# csa_ultrabus_v2.net
KiCad netlist of a schematic drawn in EAGLE
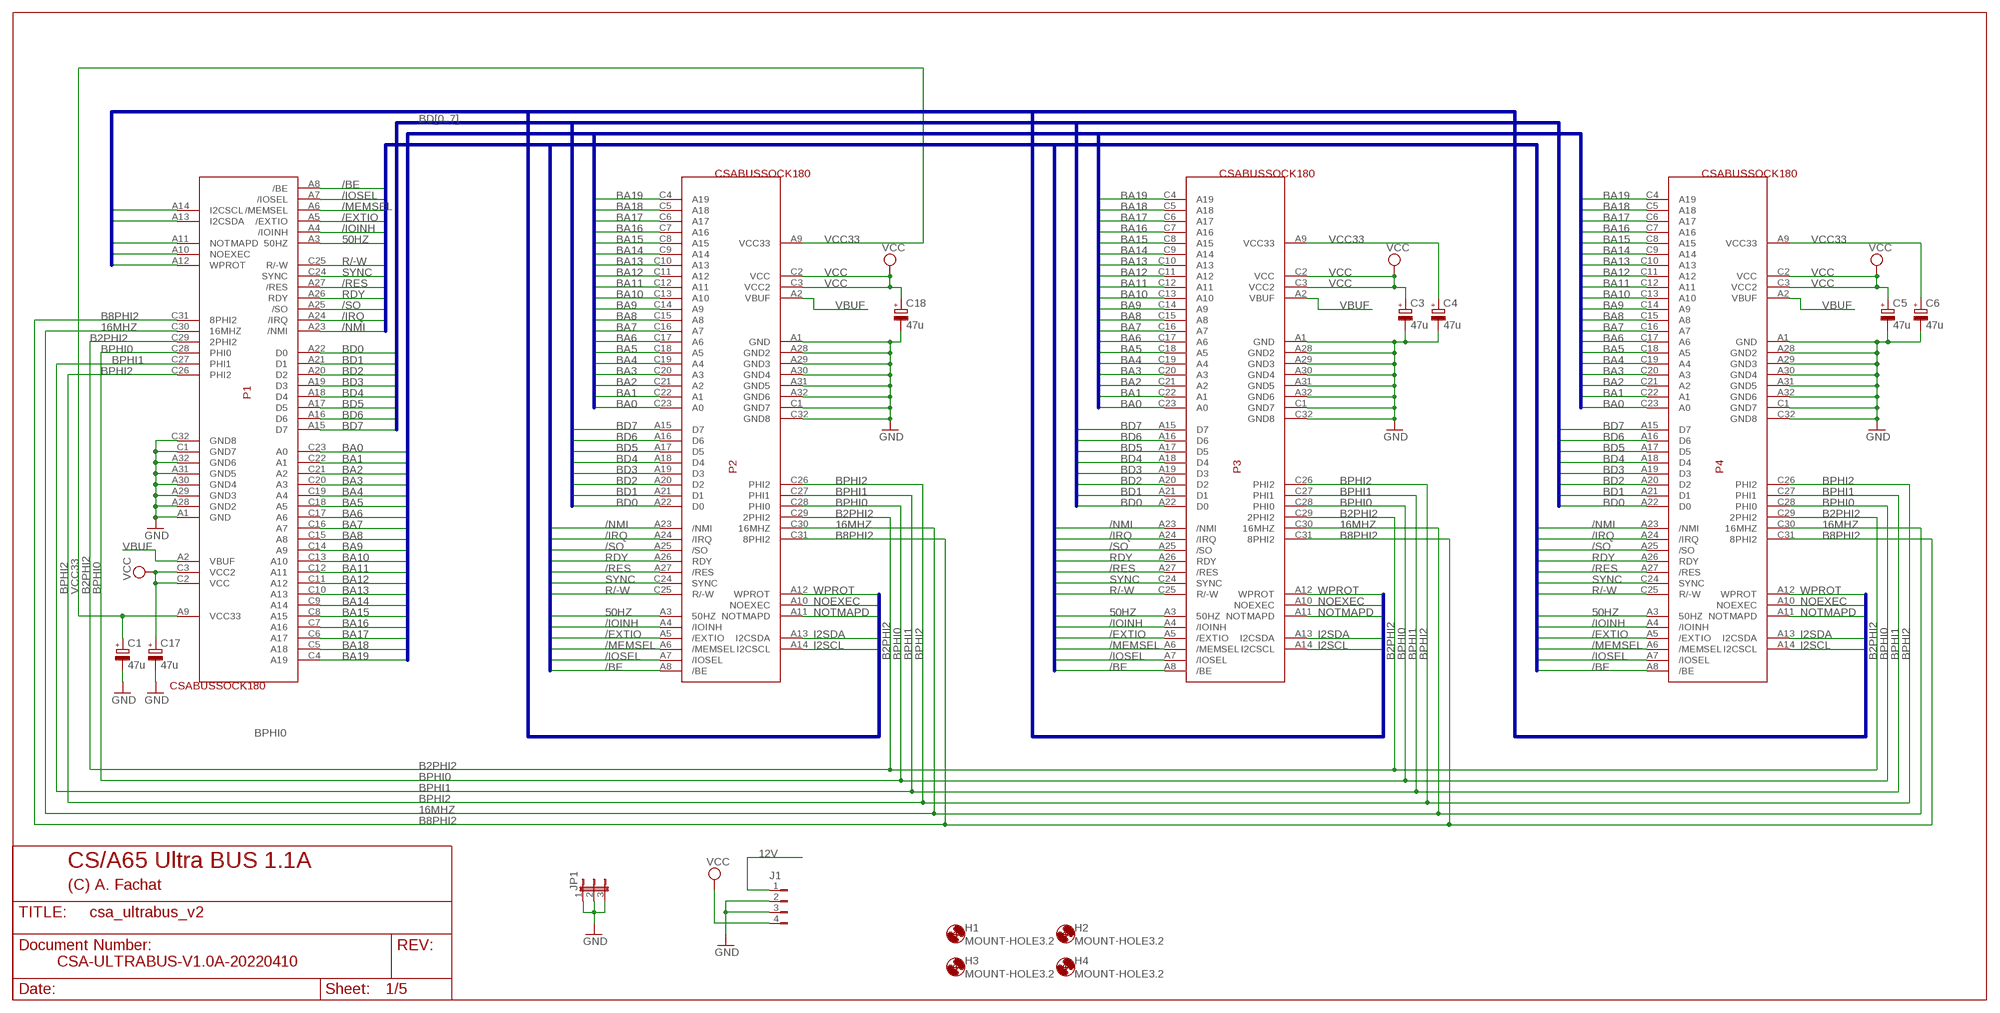
[diagram p0: schematic, sheet 1]
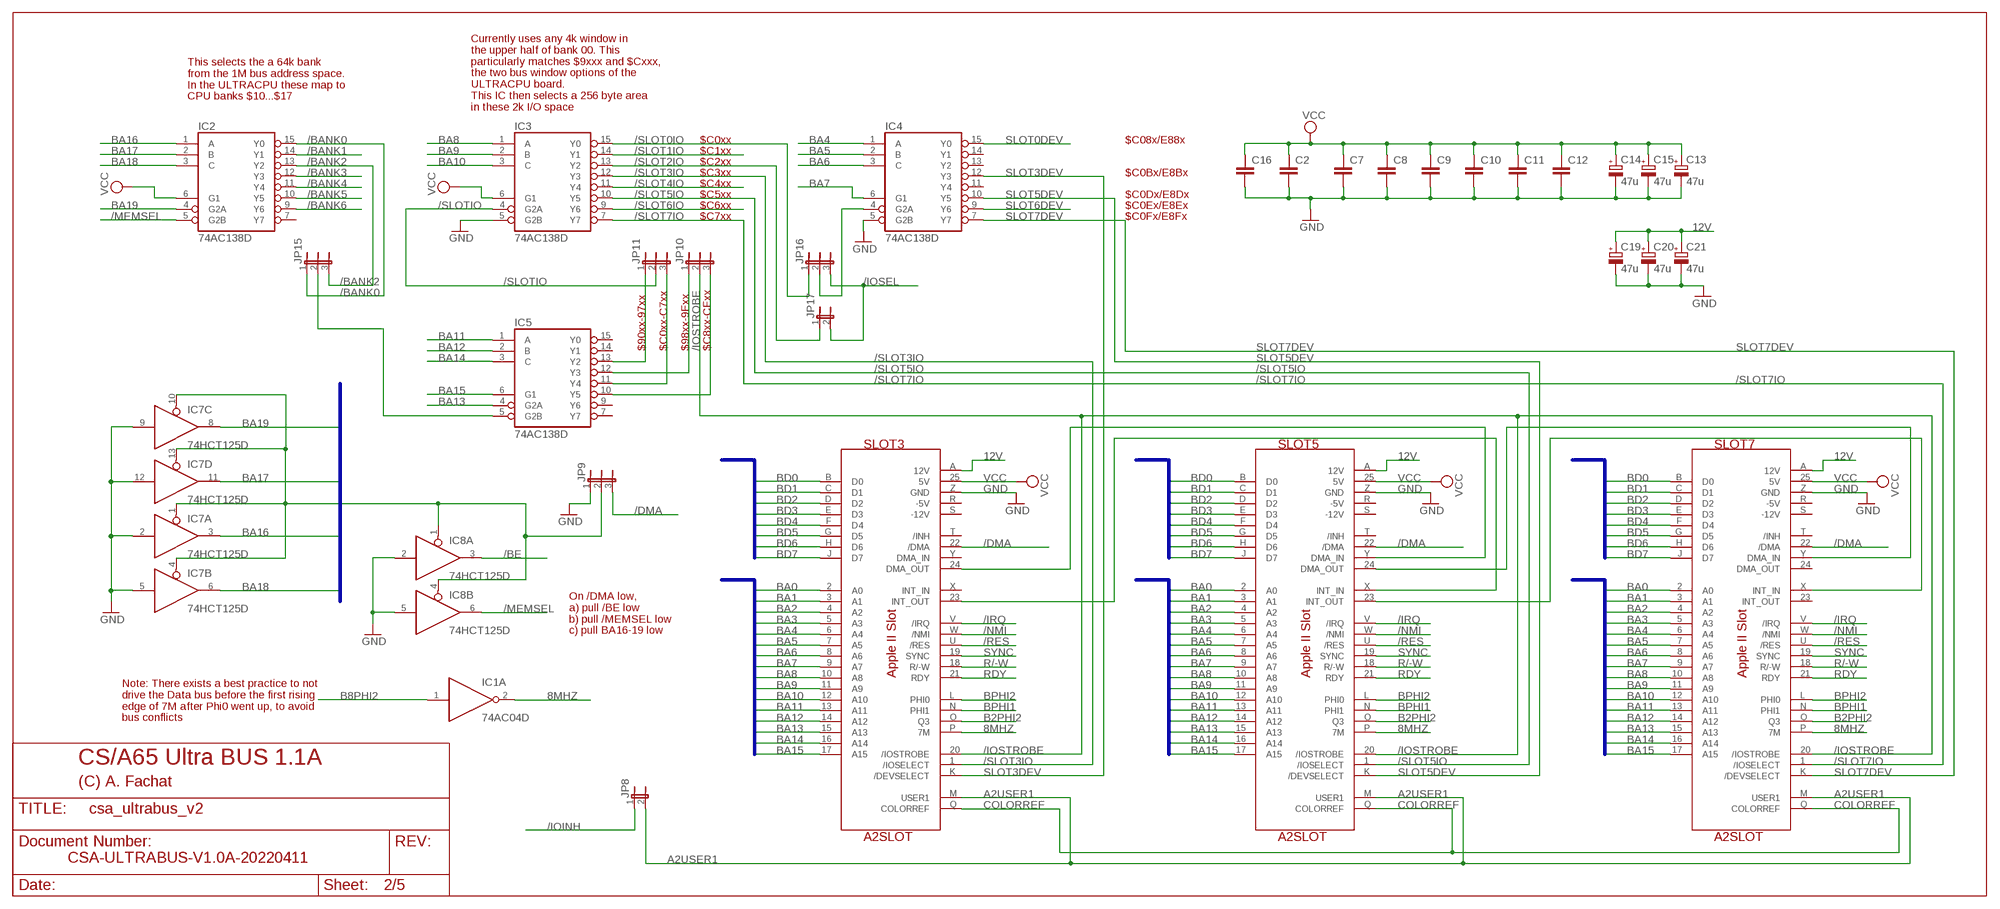
[diagram p1: schematic, sheet 2]
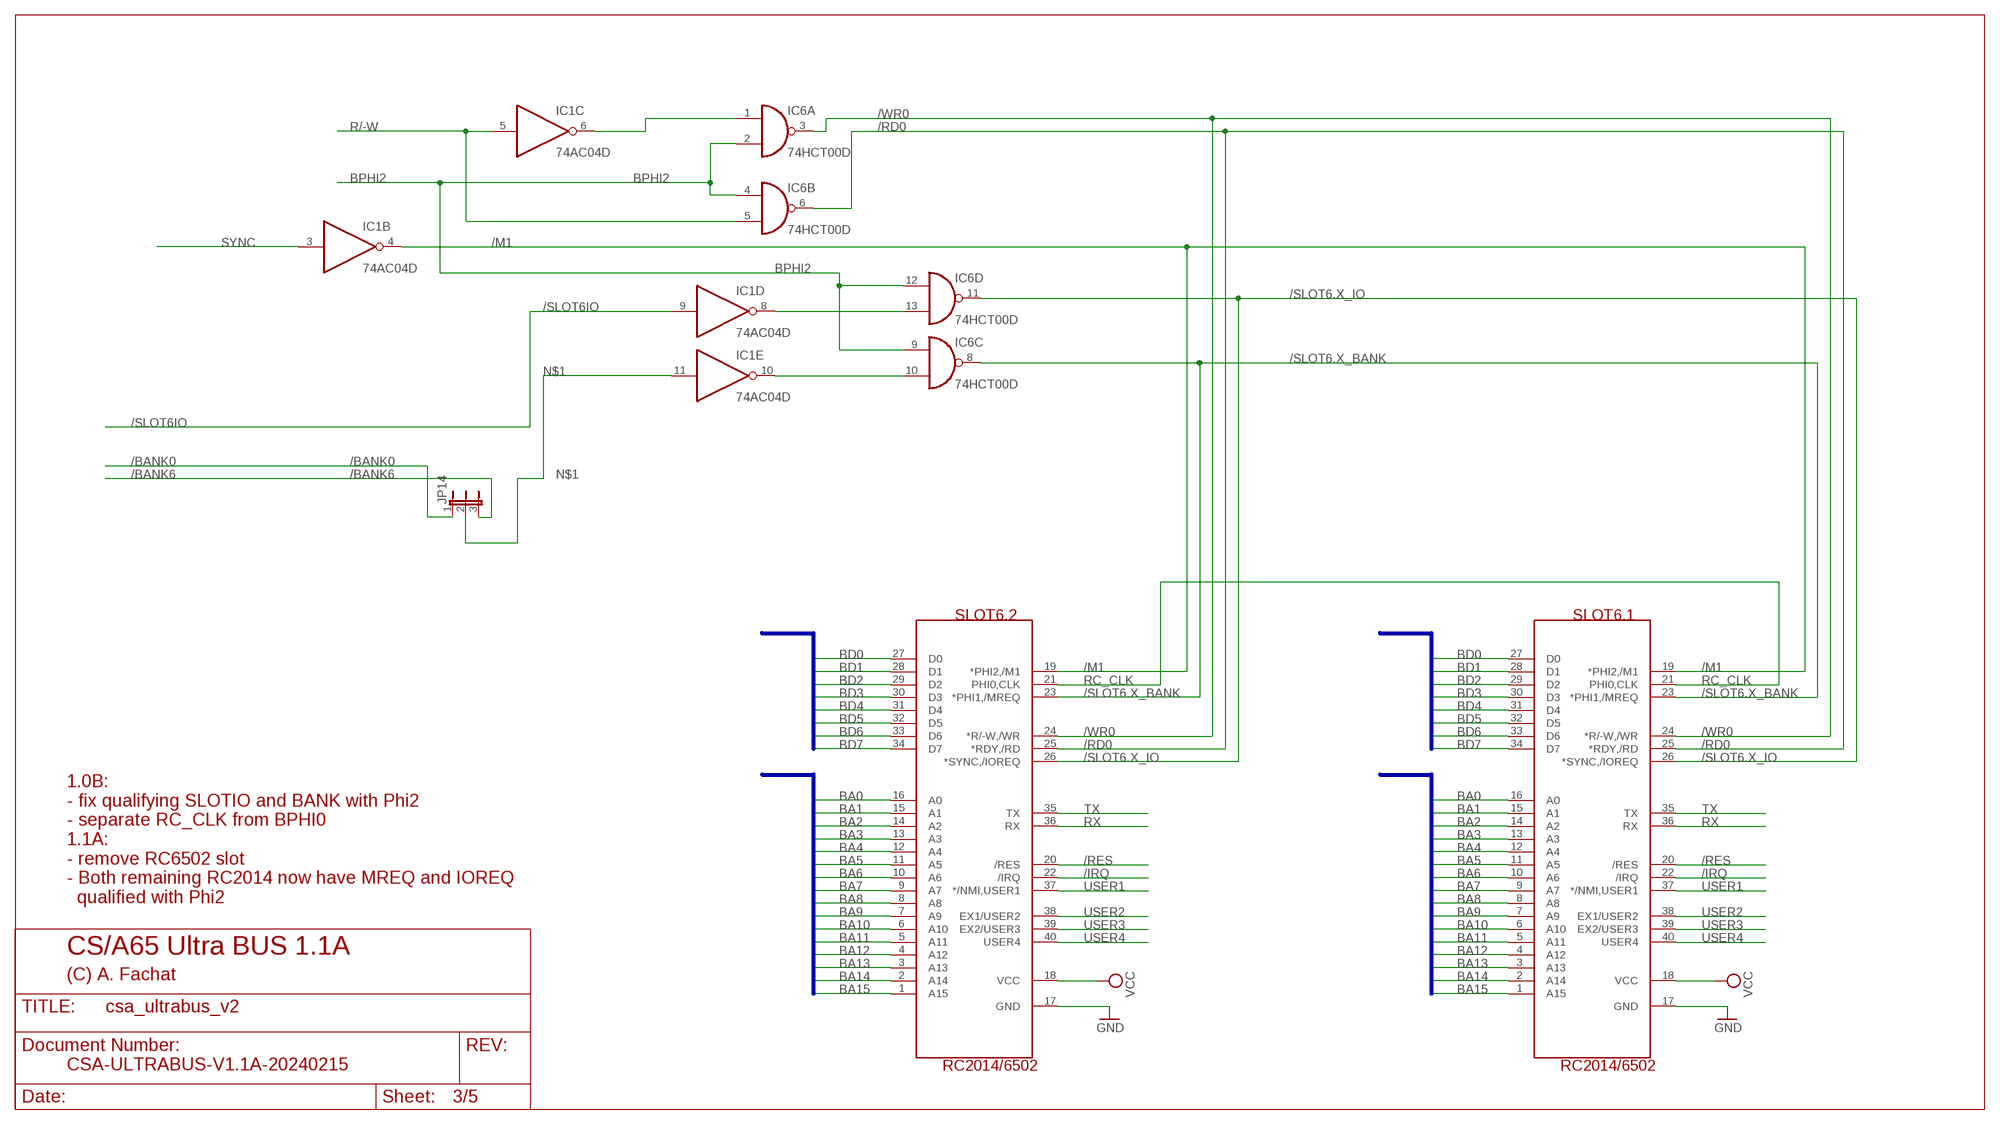
[diagram p2: schematic, sheet 3]
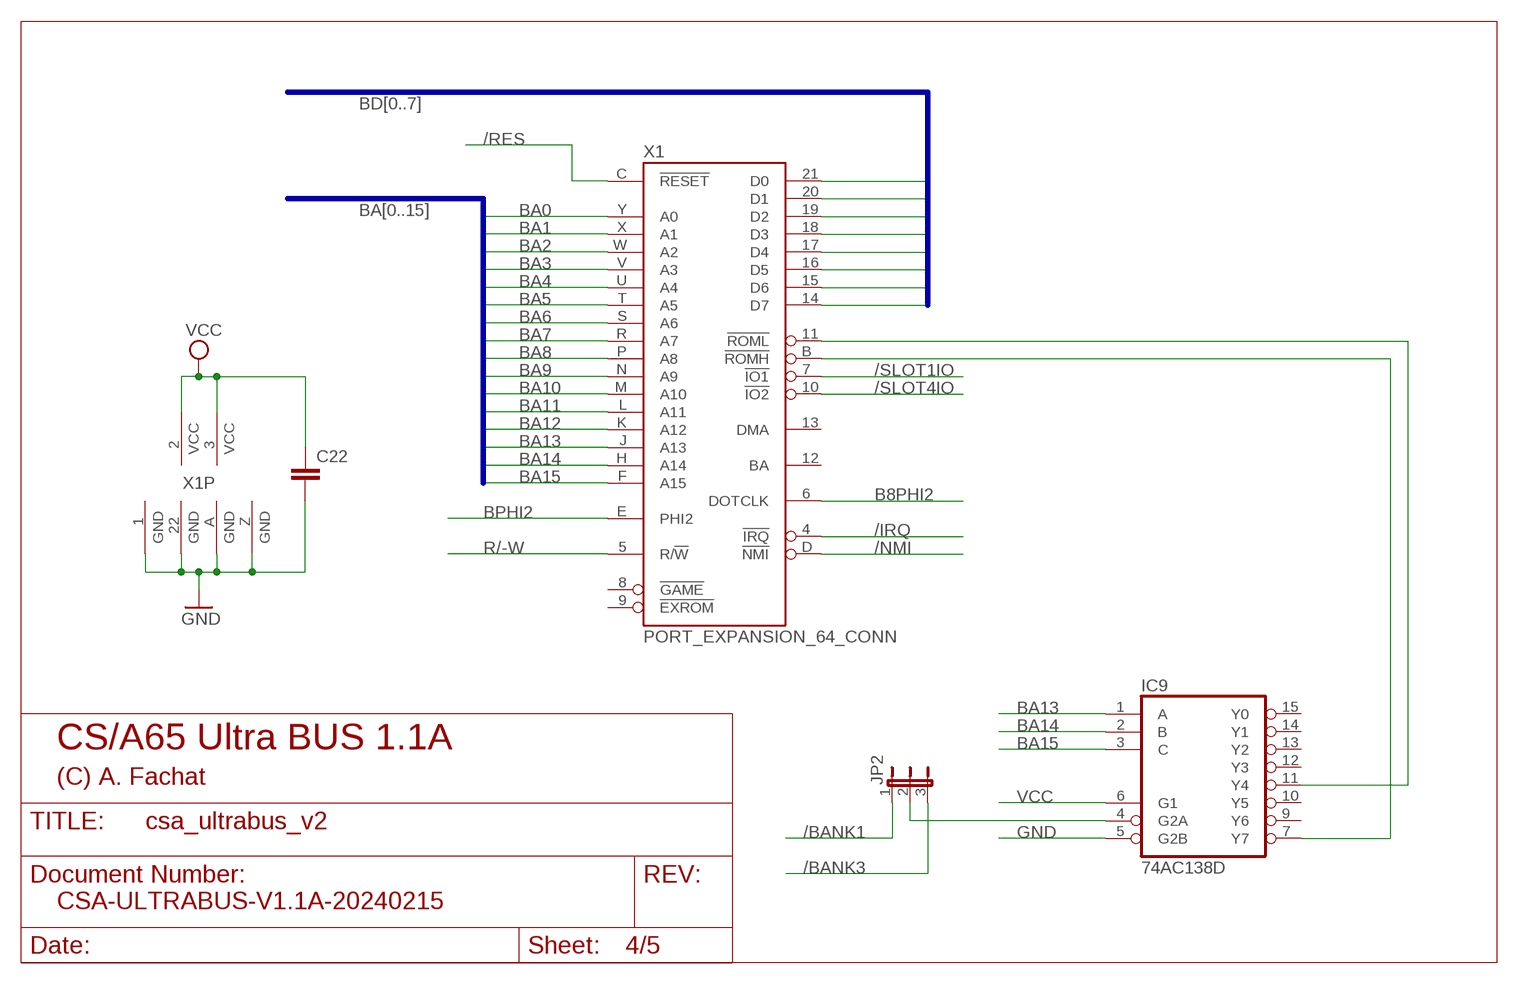
[diagram p3: schematic, sheet 4]
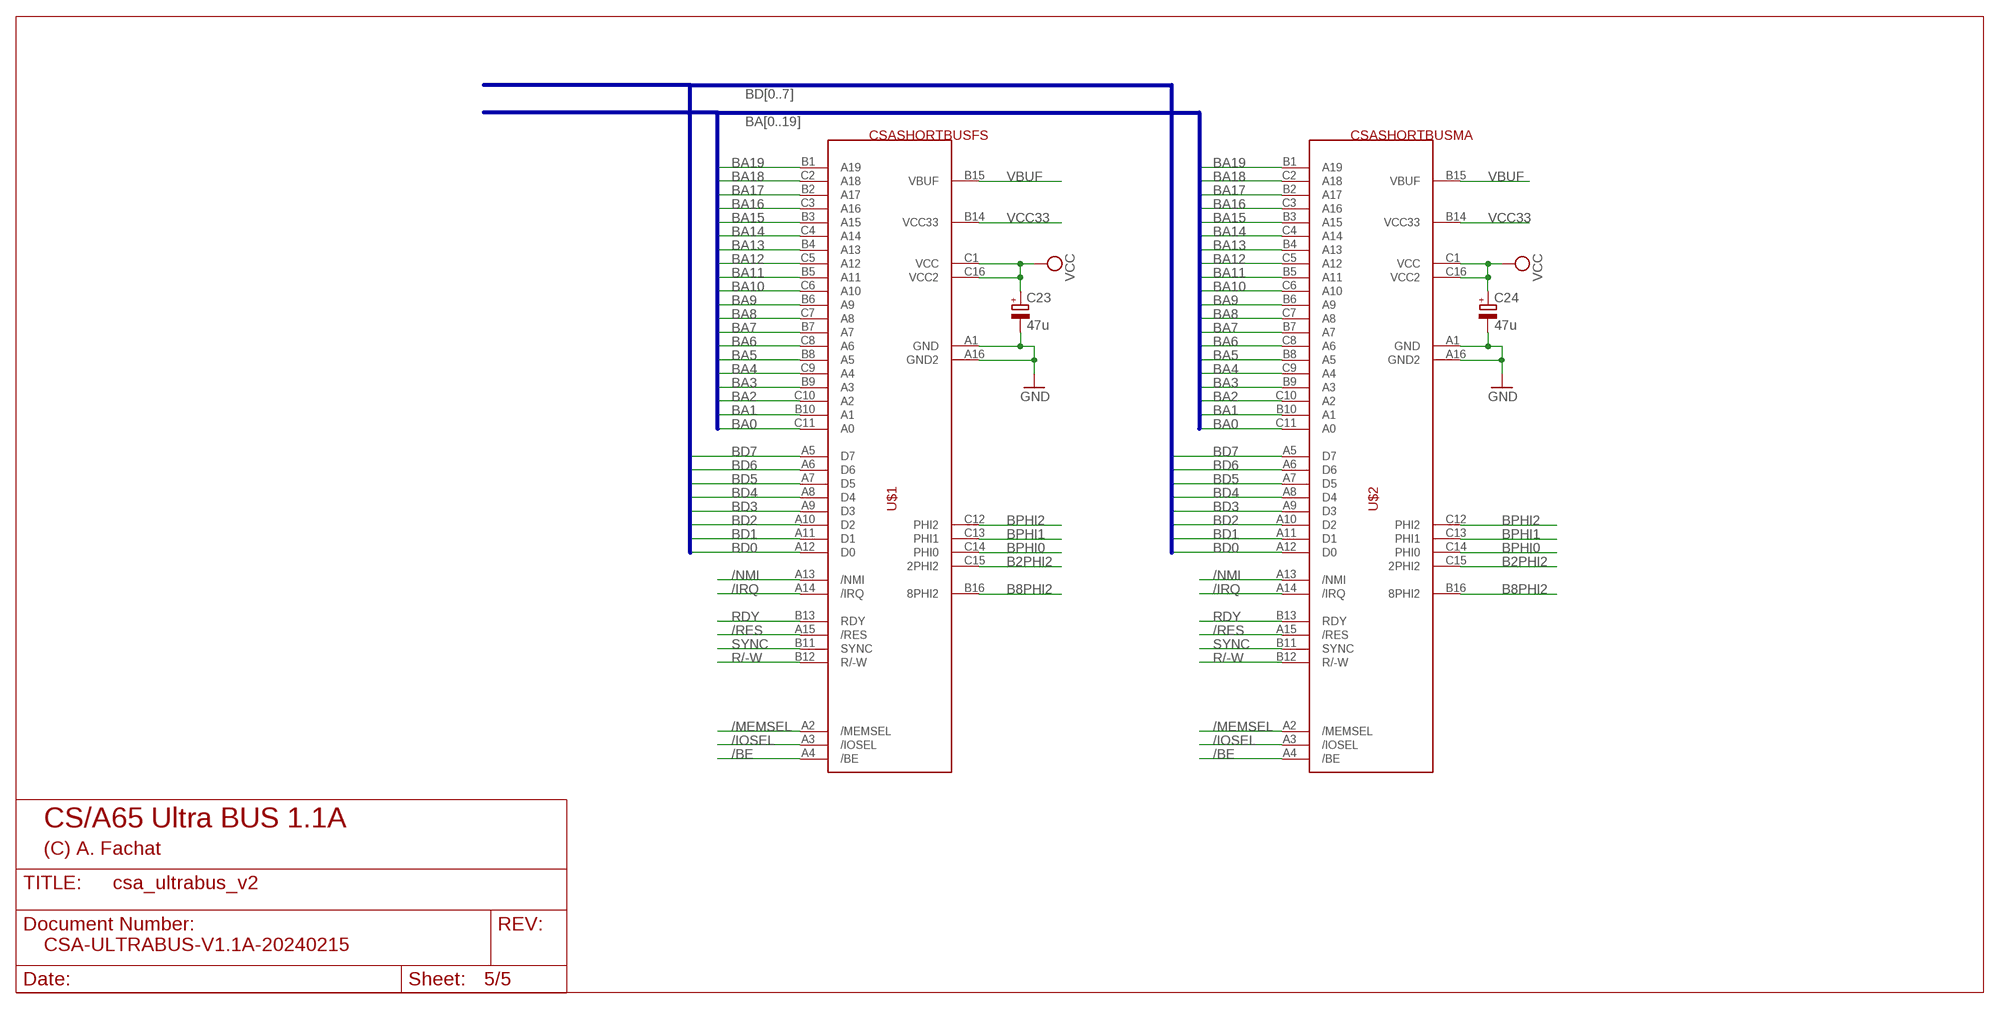
[diagram p4: schematic, sheet 5]

(export (version "E")
  (design (tool "Eeschema 10.0.6"))
  (components
    (comp (ref "C23")
      (value "47u")
      (footprint "eagle-import:E2,5-5")
      (libsource (lib "eagle-import") (part "CPOL-EUE2.5-5"))
    )
    (comp (ref "C24")
      (value "47u")
      (footprint "eagle-import:E2,5-5")
      (libsource (lib "eagle-import") (part "CPOL-EUE2.5-5"))
    )
    (comp (ref "U$1")
      (value "CSASHORTBUSFS")
      (footprint "eagle-import:FABC48S2")
      (libsource (lib "eagle-import") (part "CSASHORTBUSFS"))
    )
    (comp (ref "U$2")
      (value "CSASHORTBUSMA")
      (footprint "eagle-import:MABC48B2")
      (libsource (lib "eagle-import") (part "CSASHORTBUSMA"))
    )
    (comp (ref "IC1")
      (value "74AC04D")
      (footprint "eagle-import:SO14")
      (libsource (lib "eagle-import") (part "7404DAC"))
    )
    (comp (ref "IC6")
      (value "74HCT00D")
      (footprint "eagle-import:SO14")
      (libsource (lib "eagle-import") (part "7400DHCT"))
    )
    (comp (ref "JP14")
      (value "JP2E")
      (footprint "eagle-import:JP2")
      (libsource (lib "eagle-import") (part "JP2E"))
    )
    (comp (ref "SLOT6.1")
      (value "RC2014/6502")
      (footprint "eagle-import:SIL40")
      (libsource (lib "eagle-import") (part "RC2014/6502"))
    )
    (comp (ref "SLOT6.2")
      (value "RC2014/6502")
      (footprint "eagle-import:SIL40")
      (libsource (lib "eagle-import") (part "RC2014/6502"))
    )
    (comp (ref "C1")
      (value "47u")
      (footprint "eagle-import:E2,5-5")
      (libsource (lib "eagle-import") (part "CPOL-EUE2.5-5"))
    )
    (comp (ref "C3")
      (value "47u")
      (footprint "eagle-import:E2,5-5")
      (libsource (lib "eagle-import") (part "CPOL-EUE2.5-5"))
    )
    (comp (ref "C4")
      (value "47u")
      (footprint "eagle-import:E2,5-5")
      (libsource (lib "eagle-import") (part "CPOL-EUE2.5-5"))
    )
    (comp (ref "C5")
      (value "47u")
      (footprint "eagle-import:E2,5-5")
      (libsource (lib "eagle-import") (part "CPOL-EUE2.5-5"))
    )
    (comp (ref "C6")
      (value "47u")
      (footprint "eagle-import:E2,5-5")
      (libsource (lib "eagle-import") (part "CPOL-EUE2.5-5"))
    )
    (comp (ref "C17")
      (value "47u")
      (footprint "eagle-import:E2,5-5")
      (libsource (lib "eagle-import") (part "CPOL-EUE2.5-5"))
    )
    (comp (ref "C18")
      (value "47u")
      (footprint "eagle-import:E2,5-5")
      (libsource (lib "eagle-import") (part "CPOL-EUE2.5-5"))
    )
    (comp (ref "H1")
      (value "MOUNT-HOLE3.2")
      (footprint "eagle-import:3,2")
      (libsource (lib "eagle-import") (part "MOUNT-HOLE3.2"))
    )
    (comp (ref "H2")
      (value "MOUNT-HOLE3.2")
      (footprint "eagle-import:3,2")
      (libsource (lib "eagle-import") (part "MOUNT-HOLE3.2"))
    )
    (comp (ref "H3")
      (value "MOUNT-HOLE3.2")
      (footprint "eagle-import:3,2")
      (libsource (lib "eagle-import") (part "MOUNT-HOLE3.2"))
    )
    (comp (ref "H4")
      (value "MOUNT-HOLE3.2")
      (footprint "eagle-import:3,2")
      (libsource (lib "eagle-import") (part "MOUNT-HOLE3.2"))
    )
    (comp (ref "J1")
      (value "FLOP-4W827001")
      (footprint "eagle-import:827001")
      (libsource (lib "eagle-import") (part "FLOP-4W827001"))
    )
    (comp (ref "JP1")
      (value "JP2E")
      (footprint "eagle-import:JP2")
      (libsource (lib "eagle-import") (part "JP2E"))
    )
    (comp (ref "P1")
      (value "CSABUSSOCK180")
      (footprint "eagle-import:CSABUSSOCK180")
      (libsource (lib "eagle-import") (part "CSABUSSOCK180"))
    )
    (comp (ref "P2")
      (value "CSABUSSOCK180")
      (footprint "eagle-import:CSABUSSOCK180")
      (libsource (lib "eagle-import") (part "CSABUSSOCK180"))
    )
    (comp (ref "P3")
      (value "CSABUSSOCK180")
      (footprint "eagle-import:CSABUSSOCK180")
      (libsource (lib "eagle-import") (part "CSABUSSOCK180"))
    )
    (comp (ref "P4")
      (value "CSABUSSOCK180")
      (footprint "eagle-import:CSABUSSOCK180")
      (libsource (lib "eagle-import") (part "CSABUSSOCK180"))
    )
    (comp (ref "C2")
      (value "C-EUC0603")
      (footprint "eagle-import:C0603")
      (libsource (lib "eagle-import") (part "C-EUC0603"))
    )
    (comp (ref "C7")
      (value "C-EUC0603")
      (footprint "eagle-import:C0603")
      (libsource (lib "eagle-import") (part "C-EUC0603"))
    )
    (comp (ref "C8")
      (value "C-EUC0603")
      (footprint "eagle-import:C0603")
      (libsource (lib "eagle-import") (part "C-EUC0603"))
    )
    (comp (ref "C9")
      (value "C-EUC0603")
      (footprint "eagle-import:C0603")
      (libsource (lib "eagle-import") (part "C-EUC0603"))
    )
    (comp (ref "C10")
      (value "C-EUC0603")
      (footprint "eagle-import:C0603")
      (libsource (lib "eagle-import") (part "C-EUC0603"))
    )
    (comp (ref "C11")
      (value "C-EUC0603")
      (footprint "eagle-import:C0603")
      (libsource (lib "eagle-import") (part "C-EUC0603"))
    )
    (comp (ref "C12")
      (value "C-EUC0603")
      (footprint "eagle-import:C0603")
      (libsource (lib "eagle-import") (part "C-EUC0603"))
    )
    (comp (ref "C13")
      (value "47u")
      (footprint "eagle-import:E2,5-5")
      (libsource (lib "eagle-import") (part "CPOL-EUE2.5-5"))
    )
    (comp (ref "C14")
      (value "47u")
      (footprint "eagle-import:E2,5-5")
      (libsource (lib "eagle-import") (part "CPOL-EUE2.5-5"))
    )
    (comp (ref "C15")
      (value "47u")
      (footprint "eagle-import:E2,5-5")
      (libsource (lib "eagle-import") (part "CPOL-EUE2.5-5"))
    )
    (comp (ref "C16")
      (value "C-EUC0603")
      (footprint "eagle-import:C0603")
      (libsource (lib "eagle-import") (part "C-EUC0603"))
    )
    (comp (ref "C19")
      (value "47u")
      (footprint "eagle-import:E2,5-5")
      (libsource (lib "eagle-import") (part "CPOL-EUE2.5-5"))
    )
    (comp (ref "C20")
      (value "47u")
      (footprint "eagle-import:E2,5-5")
      (libsource (lib "eagle-import") (part "CPOL-EUE2.5-5"))
    )
    (comp (ref "C21")
      (value "47u")
      (footprint "eagle-import:E2,5-5")
      (libsource (lib "eagle-import") (part "CPOL-EUE2.5-5"))
    )
    (comp (ref "IC2")
      (value "74AC138D")
      (footprint "eagle-import:SO16")
      (libsource (lib "eagle-import") (part "74138DAC"))
    )
    (comp (ref "IC3")
      (value "74AC138D")
      (footprint "eagle-import:SO16")
      (libsource (lib "eagle-import") (part "74138DAC"))
    )
    (comp (ref "IC4")
      (value "74AC138D")
      (footprint "eagle-import:SO16")
      (libsource (lib "eagle-import") (part "74138DAC"))
    )
    (comp (ref "IC5")
      (value "74AC138D")
      (footprint "eagle-import:SO16")
      (libsource (lib "eagle-import") (part "74138DAC"))
    )
    (comp (ref "IC7")
      (value "74HCT125D")
      (footprint "eagle-import:SO14")
      (libsource (lib "eagle-import") (part "74125DHCT"))
    )
    (comp (ref "IC8")
      (value "74HCT125D")
      (footprint "eagle-import:SO14")
      (libsource (lib "eagle-import") (part "74125DHCT"))
    )
    (comp (ref "JP8")
      (value "JP1E")
      (footprint "eagle-import:JP1")
      (libsource (lib "eagle-import") (part "JP1E"))
    )
    (comp (ref "JP9")
      (value "JP2E")
      (footprint "eagle-import:JP2")
      (libsource (lib "eagle-import") (part "JP2E"))
    )
    (comp (ref "JP10")
      (value "JP2E")
      (footprint "eagle-import:JP2")
      (libsource (lib "eagle-import") (part "JP2E"))
    )
    (comp (ref "JP11")
      (value "JP2E")
      (footprint "eagle-import:JP2")
      (libsource (lib "eagle-import") (part "JP2E"))
    )
    (comp (ref "JP15")
      (value "JP2E")
      (footprint "eagle-import:JP2")
      (libsource (lib "eagle-import") (part "JP2E"))
    )
    (comp (ref "JP16")
      (value "JP2E")
      (footprint "eagle-import:JP2")
      (libsource (lib "eagle-import") (part "JP2E"))
    )
    (comp (ref "JP17")
      (value "JP1E")
      (footprint "eagle-import:JP1")
      (libsource (lib "eagle-import") (part "JP1E"))
    )
    (comp (ref "SLOT3")
      (value "A2SLOT")
      (footprint "eagle-import:FE100-25")
      (libsource (lib "eagle-import") (part "A2SLOT"))
    )
    (comp (ref "SLOT5")
      (value "A2SLOT")
      (footprint "eagle-import:FE100-25")
      (libsource (lib "eagle-import") (part "A2SLOT"))
    )
    (comp (ref "SLOT7")
      (value "A2SLOT")
      (footprint "eagle-import:FE100-25")
      (libsource (lib "eagle-import") (part "A2SLOT"))
    )
    (comp (ref "C22")
      (value "C-EUC0603")
      (footprint "eagle-import:C0603")
      (libsource (lib "eagle-import") (part "C-EUC0603"))
    )
    (comp (ref "IC9")
      (value "74AC138D")
      (footprint "eagle-import:SO16")
      (libsource (lib "eagle-import") (part "74138DAC"))
    )
    (comp (ref "JP2")
      (value "JP2E")
      (footprint "eagle-import:JP2")
      (libsource (lib "eagle-import") (part "JP2E"))
    )
    (comp (ref "X1")
      (value "PORT_EXPANSION_64_CONN")
      (footprint "eagle-import:FE100-22-2")
      (libsource (lib "eagle-import") (part "PORT_EXPANSION_64_CONN"))
    )
  )
  (nets
    (net (code "10") (name "8MHZ") (class "Default")
      (node (ref "IC1") (pin "2") (pinfunction "O_2") (pintype "output"))
      (node (ref "SLOT3") (pin "P") (pinfunction "7M_P") (pintype "bidirectional"))
      (node (ref "SLOT5") (pin "P") (pinfunction "7M_P") (pintype "bidirectional"))
      (node (ref "SLOT7") (pin "P") (pinfunction "7M_P") (pintype "bidirectional"))
    )
    (net (code "11") (name "12V") (class "Default")
      (node (ref "C19") (pin "+") (pinfunction "+_+") (pintype "passive"))
      (node (ref "C20") (pin "+") (pinfunction "+_+") (pintype "passive"))
      (node (ref "C21") (pin "+") (pinfunction "+_+") (pintype "passive"))
      (node (ref "J1") (pin "1") (pinfunction "1_1") (pintype "passive"))
      (node (ref "SLOT3") (pin "A") (pinfunction "12V_A") (pintype "bidirectional"))
      (node (ref "SLOT5") (pin "A") (pinfunction "12V_A") (pintype "bidirectional"))
      (node (ref "SLOT7") (pin "A") (pinfunction "12V_A") (pintype "bidirectional"))
    )
    (net (code "12") (name "16MHZ") (class "Default")
      (node (ref "P1") (pin "C30") (pinfunction "16MHZ_C30") (pintype "bidirectional"))
      (node (ref "P2") (pin "C30") (pinfunction "16MHZ_C30") (pintype "bidirectional"))
      (node (ref "P3") (pin "C30") (pinfunction "16MHZ_C30") (pintype "bidirectional"))
      (node (ref "P4") (pin "C30") (pinfunction "16MHZ_C30") (pintype "bidirectional"))
    )
    (net (code "13") (name "50HZ") (class "Default")
      (node (ref "P1") (pin "A3") (pinfunction "50HZ_A3") (pintype "bidirectional"))
      (node (ref "P2") (pin "A3") (pinfunction "50HZ_A3") (pintype "bidirectional"))
      (node (ref "P3") (pin "A3") (pinfunction "50HZ_A3") (pintype "bidirectional"))
      (node (ref "P4") (pin "A3") (pinfunction "50HZ_A3") (pintype "bidirectional"))
    )
    (net (code "14") (name "A2USER1") (class "Default")
      (node (ref "JP8") (pin "2") (pinfunction "2_2") (pintype "passive"))
      (node (ref "SLOT3") (pin "M") (pinfunction "USER1_M") (pintype "bidirectional"))
      (node (ref "SLOT5") (pin "M") (pinfunction "USER1_M") (pintype "bidirectional"))
      (node (ref "SLOT7") (pin "M") (pinfunction "USER1_M") (pintype "bidirectional"))
    )
    (net (code "15") (name "B2PHI2") (class "Default")
      (node (ref "P1") (pin "C29") (pinfunction "2PHI2_C29") (pintype "bidirectional"))
      (node (ref "P2") (pin "C29") (pinfunction "2PHI2_C29") (pintype "bidirectional"))
      (node (ref "P3") (pin "C29") (pinfunction "2PHI2_C29") (pintype "bidirectional"))
      (node (ref "P4") (pin "C29") (pinfunction "2PHI2_C29") (pintype "bidirectional"))
      (node (ref "SLOT3") (pin "O") (pinfunction "Q3_O") (pintype "bidirectional"))
      (node (ref "SLOT5") (pin "O") (pinfunction "Q3_O") (pintype "bidirectional"))
      (node (ref "SLOT7") (pin "O") (pinfunction "Q3_O") (pintype "bidirectional"))
      (node (ref "U$1") (pin "C15") (pinfunction "2PHI2_C15") (pintype "bidirectional"))
      (node (ref "U$2") (pin "C15") (pinfunction "2PHI2_C15") (pintype "bidirectional"))
    )
    (net (code "16") (name "B8PHI2") (class "Default")
      (node (ref "IC1") (pin "1") (pinfunction "I_1") (pintype "input"))
      (node (ref "P1") (pin "C31") (pinfunction "8PHI2_C31") (pintype "bidirectional"))
      (node (ref "P2") (pin "C31") (pinfunction "8PHI2_C31") (pintype "bidirectional"))
      (node (ref "P3") (pin "C31") (pinfunction "8PHI2_C31") (pintype "bidirectional"))
      (node (ref "P4") (pin "C31") (pinfunction "8PHI2_C31") (pintype "bidirectional"))
      (node (ref "U$1") (pin "B16") (pinfunction "8PHI2_B16") (pintype "bidirectional"))
      (node (ref "U$2") (pin "B16") (pinfunction "8PHI2_B16") (pintype "bidirectional"))
      (node (ref "X1") (pin "6") (pinfunction "DOTCLK_6") (pintype "input"))
    )
    (net (code "17") (name "BA0") (class "Default")
      (node (ref "P1") (pin "C23") (pinfunction "A0_C23") (pintype "bidirectional"))
      (node (ref "P2") (pin "C23") (pinfunction "A0_C23") (pintype "bidirectional"))
      (node (ref "P3") (pin "C23") (pinfunction "A0_C23") (pintype "bidirectional"))
      (node (ref "P4") (pin "C23") (pinfunction "A0_C23") (pintype "bidirectional"))
      (node (ref "SLOT3") (pin "2") (pinfunction "A0_2") (pintype "bidirectional"))
      (node (ref "SLOT5") (pin "2") (pinfunction "A0_2") (pintype "bidirectional"))
      (node (ref "SLOT6.1") (pin "16") (pinfunction "A0_16") (pintype "bidirectional"))
      (node (ref "SLOT6.2") (pin "16") (pinfunction "A0_16") (pintype "bidirectional"))
      (node (ref "SLOT7") (pin "2") (pinfunction "A0_2") (pintype "bidirectional"))
      (node (ref "U$1") (pin "C11") (pinfunction "A0_C11") (pintype "bidirectional"))
      (node (ref "U$2") (pin "C11") (pinfunction "A0_C11") (pintype "bidirectional"))
      (node (ref "X1") (pin "Y") (pinfunction "A0_Y") (pintype "bidirectional"))
    )
    (net (code "18") (name "BA1") (class "Default")
      (node (ref "P1") (pin "C22") (pinfunction "A1_C22") (pintype "bidirectional"))
      (node (ref "P2") (pin "C22") (pinfunction "A1_C22") (pintype "bidirectional"))
      (node (ref "P3") (pin "C22") (pinfunction "A1_C22") (pintype "bidirectional"))
      (node (ref "P4") (pin "C22") (pinfunction "A1_C22") (pintype "bidirectional"))
      (node (ref "SLOT3") (pin "3") (pinfunction "A1_3") (pintype "bidirectional"))
      (node (ref "SLOT5") (pin "3") (pinfunction "A1_3") (pintype "bidirectional"))
      (node (ref "SLOT6.1") (pin "15") (pinfunction "A1_15") (pintype "bidirectional"))
      (node (ref "SLOT6.2") (pin "15") (pinfunction "A1_15") (pintype "bidirectional"))
      (node (ref "SLOT7") (pin "3") (pinfunction "A1_3") (pintype "bidirectional"))
      (node (ref "U$1") (pin "B10") (pinfunction "A1_B10") (pintype "bidirectional"))
      (node (ref "U$2") (pin "B10") (pinfunction "A1_B10") (pintype "bidirectional"))
      (node (ref "X1") (pin "X") (pinfunction "A1_X") (pintype "bidirectional"))
    )
    (net (code "19") (name "BA2") (class "Default")
      (node (ref "P1") (pin "C21") (pinfunction "A2_C21") (pintype "bidirectional"))
      (node (ref "P2") (pin "C21") (pinfunction "A2_C21") (pintype "bidirectional"))
      (node (ref "P3") (pin "C21") (pinfunction "A2_C21") (pintype "bidirectional"))
      (node (ref "P4") (pin "C21") (pinfunction "A2_C21") (pintype "bidirectional"))
      (node (ref "SLOT3") (pin "4") (pinfunction "A2_4") (pintype "bidirectional"))
      (node (ref "SLOT5") (pin "4") (pinfunction "A2_4") (pintype "bidirectional"))
      (node (ref "SLOT6.1") (pin "14") (pinfunction "A2_14") (pintype "bidirectional"))
      (node (ref "SLOT6.2") (pin "14") (pinfunction "A2_14") (pintype "bidirectional"))
      (node (ref "SLOT7") (pin "4") (pinfunction "A2_4") (pintype "bidirectional"))
      (node (ref "U$1") (pin "C10") (pinfunction "A2_C10") (pintype "bidirectional"))
      (node (ref "U$2") (pin "C10") (pinfunction "A2_C10") (pintype "bidirectional"))
      (node (ref "X1") (pin "W") (pinfunction "A2_W") (pintype "bidirectional"))
    )
    (net (code "20") (name "BA3") (class "Default")
      (node (ref "P1") (pin "C20") (pinfunction "A3_C20") (pintype "bidirectional"))
      (node (ref "P2") (pin "C20") (pinfunction "A3_C20") (pintype "bidirectional"))
      (node (ref "P3") (pin "C20") (pinfunction "A3_C20") (pintype "bidirectional"))
      (node (ref "P4") (pin "C20") (pinfunction "A3_C20") (pintype "bidirectional"))
      (node (ref "SLOT3") (pin "5") (pinfunction "A3_5") (pintype "bidirectional"))
      (node (ref "SLOT5") (pin "5") (pinfunction "A3_5") (pintype "bidirectional"))
      (node (ref "SLOT6.1") (pin "13") (pinfunction "A3_13") (pintype "bidirectional"))
      (node (ref "SLOT6.2") (pin "13") (pinfunction "A3_13") (pintype "bidirectional"))
      (node (ref "SLOT7") (pin "5") (pinfunction "A3_5") (pintype "bidirectional"))
      (node (ref "U$1") (pin "B9") (pinfunction "A3_B9") (pintype "bidirectional"))
      (node (ref "U$2") (pin "B9") (pinfunction "A3_B9") (pintype "bidirectional"))
      (node (ref "X1") (pin "V") (pinfunction "A3_V") (pintype "bidirectional"))
    )
    (net (code "21") (name "BA4") (class "Default")
      (node (ref "IC4") (pin "1") (pinfunction "A_1") (pintype "input"))
      (node (ref "P1") (pin "C19") (pinfunction "A4_C19") (pintype "bidirectional"))
      (node (ref "P2") (pin "C19") (pinfunction "A4_C19") (pintype "bidirectional"))
      (node (ref "P3") (pin "C19") (pinfunction "A4_C19") (pintype "bidirectional"))
      (node (ref "P4") (pin "C19") (pinfunction "A4_C19") (pintype "bidirectional"))
      (node (ref "SLOT3") (pin "6") (pinfunction "A4_6") (pintype "bidirectional"))
      (node (ref "SLOT5") (pin "6") (pinfunction "A4_6") (pintype "bidirectional"))
      (node (ref "SLOT6.1") (pin "12") (pinfunction "A4_12") (pintype "bidirectional"))
      (node (ref "SLOT6.2") (pin "12") (pinfunction "A4_12") (pintype "bidirectional"))
      (node (ref "SLOT7") (pin "6") (pinfunction "A4_6") (pintype "bidirectional"))
      (node (ref "U$1") (pin "C9") (pinfunction "A4_C9") (pintype "bidirectional"))
      (node (ref "U$2") (pin "C9") (pinfunction "A4_C9") (pintype "bidirectional"))
      (node (ref "X1") (pin "U") (pinfunction "A4_U") (pintype "bidirectional"))
    )
    (net (code "22") (name "BA5") (class "Default")
      (node (ref "IC4") (pin "2") (pinfunction "B_2") (pintype "input"))
      (node (ref "P1") (pin "C18") (pinfunction "A5_C18") (pintype "bidirectional"))
      (node (ref "P2") (pin "C18") (pinfunction "A5_C18") (pintype "bidirectional"))
      (node (ref "P3") (pin "C18") (pinfunction "A5_C18") (pintype "bidirectional"))
      (node (ref "P4") (pin "C18") (pinfunction "A5_C18") (pintype "bidirectional"))
      (node (ref "SLOT3") (pin "7") (pinfunction "A5_7") (pintype "bidirectional"))
      (node (ref "SLOT5") (pin "7") (pinfunction "A5_7") (pintype "bidirectional"))
      (node (ref "SLOT6.1") (pin "11") (pinfunction "A5_11") (pintype "bidirectional"))
      (node (ref "SLOT6.2") (pin "11") (pinfunction "A5_11") (pintype "bidirectional"))
      (node (ref "SLOT7") (pin "7") (pinfunction "A5_7") (pintype "bidirectional"))
      (node (ref "U$1") (pin "B8") (pinfunction "A5_B8") (pintype "bidirectional"))
      (node (ref "U$2") (pin "B8") (pinfunction "A5_B8") (pintype "bidirectional"))
      (node (ref "X1") (pin "T") (pinfunction "A5_T") (pintype "bidirectional"))
    )
    (net (code "23") (name "BA6") (class "Default")
      (node (ref "IC4") (pin "3") (pinfunction "C_3") (pintype "input"))
      (node (ref "P1") (pin "C17") (pinfunction "A6_C17") (pintype "bidirectional"))
      (node (ref "P2") (pin "C17") (pinfunction "A6_C17") (pintype "bidirectional"))
      (node (ref "P3") (pin "C17") (pinfunction "A6_C17") (pintype "bidirectional"))
      (node (ref "P4") (pin "C17") (pinfunction "A6_C17") (pintype "bidirectional"))
      (node (ref "SLOT3") (pin "8") (pinfunction "A6_8") (pintype "bidirectional"))
      (node (ref "SLOT5") (pin "8") (pinfunction "A6_8") (pintype "bidirectional"))
      (node (ref "SLOT6.1") (pin "10") (pinfunction "A6_10") (pintype "bidirectional"))
      (node (ref "SLOT6.2") (pin "10") (pinfunction "A6_10") (pintype "bidirectional"))
      (node (ref "SLOT7") (pin "8") (pinfunction "A6_8") (pintype "bidirectional"))
      (node (ref "U$1") (pin "C8") (pinfunction "A6_C8") (pintype "bidirectional"))
      (node (ref "U$2") (pin "C8") (pinfunction "A6_C8") (pintype "bidirectional"))
      (node (ref "X1") (pin "S") (pinfunction "A6_S") (pintype "bidirectional"))
    )
    (net (code "24") (name "BA7") (class "Default")
      (node (ref "IC4") (pin "6") (pinfunction "G1_6") (pintype "input"))
      (node (ref "P1") (pin "C16") (pinfunction "A7_C16") (pintype "bidirectional"))
      (node (ref "P2") (pin "C16") (pinfunction "A7_C16") (pintype "bidirectional"))
      (node (ref "P3") (pin "C16") (pinfunction "A7_C16") (pintype "bidirectional"))
      (node (ref "P4") (pin "C16") (pinfunction "A7_C16") (pintype "bidirectional"))
      (node (ref "SLOT3") (pin "9") (pinfunction "A7_9") (pintype "bidirectional"))
      (node (ref "SLOT5") (pin "9") (pinfunction "A7_9") (pintype "bidirectional"))
      (node (ref "SLOT6.1") (pin "9") (pinfunction "A7_9") (pintype "bidirectional"))
      (node (ref "SLOT6.2") (pin "9") (pinfunction "A7_9") (pintype "bidirectional"))
      (node (ref "SLOT7") (pin "9") (pinfunction "A7_9") (pintype "bidirectional"))
      (node (ref "U$1") (pin "B7") (pinfunction "A7_B7") (pintype "bidirectional"))
      (node (ref "U$2") (pin "B7") (pinfunction "A7_B7") (pintype "bidirectional"))
      (node (ref "X1") (pin "R") (pinfunction "A7_R") (pintype "bidirectional"))
    )
    (net (code "25") (name "BA8") (class "Default")
      (node (ref "IC3") (pin "1") (pinfunction "A_1") (pintype "input"))
      (node (ref "P1") (pin "C15") (pinfunction "A8_C15") (pintype "bidirectional"))
      (node (ref "P2") (pin "C15") (pinfunction "A8_C15") (pintype "bidirectional"))
      (node (ref "P3") (pin "C15") (pinfunction "A8_C15") (pintype "bidirectional"))
      (node (ref "P4") (pin "C15") (pinfunction "A8_C15") (pintype "bidirectional"))
      (node (ref "SLOT3") (pin "10") (pinfunction "A8_10") (pintype "bidirectional"))
      (node (ref "SLOT5") (pin "10") (pinfunction "A8_10") (pintype "bidirectional"))
      (node (ref "SLOT6.1") (pin "8") (pinfunction "A8_8") (pintype "bidirectional"))
      (node (ref "SLOT6.2") (pin "8") (pinfunction "A8_8") (pintype "bidirectional"))
      (node (ref "SLOT7") (pin "10") (pinfunction "A8_10") (pintype "bidirectional"))
      (node (ref "U$1") (pin "C7") (pinfunction "A8_C7") (pintype "bidirectional"))
      (node (ref "U$2") (pin "C7") (pinfunction "A8_C7") (pintype "bidirectional"))
      (node (ref "X1") (pin "P") (pinfunction "A8_P") (pintype "bidirectional"))
    )
    (net (code "26") (name "BA9") (class "Default")
      (node (ref "IC3") (pin "2") (pinfunction "B_2") (pintype "input"))
      (node (ref "P1") (pin "C14") (pinfunction "A9_C14") (pintype "bidirectional"))
      (node (ref "P2") (pin "C14") (pinfunction "A9_C14") (pintype "bidirectional"))
      (node (ref "P3") (pin "C14") (pinfunction "A9_C14") (pintype "bidirectional"))
      (node (ref "P4") (pin "C14") (pinfunction "A9_C14") (pintype "bidirectional"))
      (node (ref "SLOT3") (pin "11") (pinfunction "A9_11") (pintype "bidirectional"))
      (node (ref "SLOT5") (pin "11") (pinfunction "A9_11") (pintype "bidirectional"))
      (node (ref "SLOT6.1") (pin "7") (pinfunction "A9_7") (pintype "bidirectional"))
      (node (ref "SLOT6.2") (pin "7") (pinfunction "A9_7") (pintype "bidirectional"))
      (node (ref "SLOT7") (pin "11") (pinfunction "A9_11") (pintype "bidirectional"))
      (node (ref "U$1") (pin "B6") (pinfunction "A9_B6") (pintype "bidirectional"))
      (node (ref "U$2") (pin "B6") (pinfunction "A9_B6") (pintype "bidirectional"))
      (node (ref "X1") (pin "N") (pinfunction "A9_N") (pintype "bidirectional"))
    )
    (net (code "27") (name "BA10") (class "Default")
      (node (ref "IC3") (pin "3") (pinfunction "C_3") (pintype "input"))
      (node (ref "P1") (pin "C13") (pinfunction "A10_C13") (pintype "bidirectional"))
      (node (ref "P2") (pin "C13") (pinfunction "A10_C13") (pintype "bidirectional"))
      (node (ref "P3") (pin "C13") (pinfunction "A10_C13") (pintype "bidirectional"))
      (node (ref "P4") (pin "C13") (pinfunction "A10_C13") (pintype "bidirectional"))
      (node (ref "SLOT3") (pin "12") (pinfunction "A10_12") (pintype "bidirectional"))
      (node (ref "SLOT5") (pin "12") (pinfunction "A10_12") (pintype "bidirectional"))
      (node (ref "SLOT6.1") (pin "6") (pinfunction "A10_6") (pintype "bidirectional"))
      (node (ref "SLOT6.2") (pin "6") (pinfunction "A10_6") (pintype "bidirectional"))
      (node (ref "SLOT7") (pin "12") (pinfunction "A10_12") (pintype "bidirectional"))
      (node (ref "U$1") (pin "C6") (pinfunction "A10_C6") (pintype "bidirectional"))
      (node (ref "U$2") (pin "C6") (pinfunction "A10_C6") (pintype "bidirectional"))
      (node (ref "X1") (pin "M") (pinfunction "A10_M") (pintype "bidirectional"))
    )
    (net (code "28") (name "BA11") (class "Default")
      (node (ref "IC5") (pin "1") (pinfunction "A_1") (pintype "input"))
      (node (ref "P1") (pin "C12") (pinfunction "A11_C12") (pintype "bidirectional"))
      (node (ref "P2") (pin "C12") (pinfunction "A11_C12") (pintype "bidirectional"))
      (node (ref "P3") (pin "C12") (pinfunction "A11_C12") (pintype "bidirectional"))
      (node (ref "P4") (pin "C12") (pinfunction "A11_C12") (pintype "bidirectional"))
      (node (ref "SLOT3") (pin "13") (pinfunction "A11_13") (pintype "bidirectional"))
      (node (ref "SLOT5") (pin "13") (pinfunction "A11_13") (pintype "bidirectional"))
      (node (ref "SLOT6.1") (pin "5") (pinfunction "A11_5") (pintype "bidirectional"))
      (node (ref "SLOT6.2") (pin "5") (pinfunction "A11_5") (pintype "bidirectional"))
      (node (ref "SLOT7") (pin "13") (pinfunction "A11_13") (pintype "bidirectional"))
      (node (ref "U$1") (pin "B5") (pinfunction "A11_B5") (pintype "bidirectional"))
      (node (ref "U$2") (pin "B5") (pinfunction "A11_B5") (pintype "bidirectional"))
      (node (ref "X1") (pin "L") (pinfunction "A11_L") (pintype "bidirectional"))
    )
    (net (code "29") (name "BA12") (class "Default")
      (node (ref "IC5") (pin "2") (pinfunction "B_2") (pintype "input"))
      (node (ref "P1") (pin "C11") (pinfunction "A12_C11") (pintype "bidirectional"))
      (node (ref "P2") (pin "C11") (pinfunction "A12_C11") (pintype "bidirectional"))
      (node (ref "P3") (pin "C11") (pinfunction "A12_C11") (pintype "bidirectional"))
      (node (ref "P4") (pin "C11") (pinfunction "A12_C11") (pintype "bidirectional"))
      (node (ref "SLOT3") (pin "14") (pinfunction "A12_14") (pintype "bidirectional"))
      (node (ref "SLOT5") (pin "14") (pinfunction "A12_14") (pintype "bidirectional"))
      (node (ref "SLOT6.1") (pin "4") (pinfunction "A12_4") (pintype "bidirectional"))
      (node (ref "SLOT6.2") (pin "4") (pinfunction "A12_4") (pintype "bidirectional"))
      (node (ref "SLOT7") (pin "14") (pinfunction "A12_14") (pintype "bidirectional"))
      (node (ref "U$1") (pin "C5") (pinfunction "A12_C5") (pintype "bidirectional"))
      (node (ref "U$2") (pin "C5") (pinfunction "A12_C5") (pintype "bidirectional"))
      (node (ref "X1") (pin "K") (pinfunction "A12_K") (pintype "bidirectional"))
    )
    (net (code "30") (name "BA13") (class "Default")
      (node (ref "IC5") (pin "4") (pinfunction "G2A_4") (pintype "input"))
      (node (ref "IC9") (pin "1") (pinfunction "A_1") (pintype "input"))
      (node (ref "P1") (pin "C10") (pinfunction "A13_C10") (pintype "bidirectional"))
      (node (ref "P2") (pin "C10") (pinfunction "A13_C10") (pintype "bidirectional"))
      (node (ref "P3") (pin "C10") (pinfunction "A13_C10") (pintype "bidirectional"))
      (node (ref "P4") (pin "C10") (pinfunction "A13_C10") (pintype "bidirectional"))
      (node (ref "SLOT3") (pin "15") (pinfunction "A13_15") (pintype "bidirectional"))
      (node (ref "SLOT5") (pin "15") (pinfunction "A13_15") (pintype "bidirectional"))
      (node (ref "SLOT6.1") (pin "3") (pinfunction "A13_3") (pintype "bidirectional"))
      (node (ref "SLOT6.2") (pin "3") (pinfunction "A13_3") (pintype "bidirectional"))
      (node (ref "SLOT7") (pin "15") (pinfunction "A13_15") (pintype "bidirectional"))
      (node (ref "U$1") (pin "B4") (pinfunction "A13_B4") (pintype "bidirectional"))
      (node (ref "U$2") (pin "B4") (pinfunction "A13_B4") (pintype "bidirectional"))
      (node (ref "X1") (pin "J") (pinfunction "A13_J") (pintype "bidirectional"))
    )
    (net (code "31") (name "BA14") (class "Default")
      (node (ref "IC5") (pin "3") (pinfunction "C_3") (pintype "input"))
      (node (ref "IC9") (pin "2") (pinfunction "B_2") (pintype "input"))
      (node (ref "P1") (pin "C9") (pinfunction "A14_C9") (pintype "bidirectional"))
      (node (ref "P2") (pin "C9") (pinfunction "A14_C9") (pintype "bidirectional"))
      (node (ref "P3") (pin "C9") (pinfunction "A14_C9") (pintype "bidirectional"))
      (node (ref "P4") (pin "C9") (pinfunction "A14_C9") (pintype "bidirectional"))
      (node (ref "SLOT3") (pin "16") (pinfunction "A14_16") (pintype "bidirectional"))
      (node (ref "SLOT5") (pin "16") (pinfunction "A14_16") (pintype "bidirectional"))
      (node (ref "SLOT6.1") (pin "2") (pinfunction "A14_2") (pintype "bidirectional"))
      (node (ref "SLOT6.2") (pin "2") (pinfunction "A14_2") (pintype "bidirectional"))
      (node (ref "SLOT7") (pin "16") (pinfunction "A14_16") (pintype "bidirectional"))
      (node (ref "U$1") (pin "C4") (pinfunction "A14_C4") (pintype "bidirectional"))
      (node (ref "U$2") (pin "C4") (pinfunction "A14_C4") (pintype "bidirectional"))
      (node (ref "X1") (pin "H") (pinfunction "A14_H") (pintype "bidirectional"))
    )
    (net (code "32") (name "BA15") (class "Default")
      (node (ref "IC5") (pin "6") (pinfunction "G1_6") (pintype "input"))
      (node (ref "IC9") (pin "3") (pinfunction "C_3") (pintype "input"))
      (node (ref "P1") (pin "C8") (pinfunction "A15_C8") (pintype "bidirectional"))
      (node (ref "P2") (pin "C8") (pinfunction "A15_C8") (pintype "bidirectional"))
      (node (ref "P3") (pin "C8") (pinfunction "A15_C8") (pintype "bidirectional"))
      (node (ref "P4") (pin "C8") (pinfunction "A15_C8") (pintype "bidirectional"))
      (node (ref "SLOT3") (pin "17") (pinfunction "A15_17") (pintype "bidirectional"))
      (node (ref "SLOT5") (pin "17") (pinfunction "A15_17") (pintype "bidirectional"))
      (node (ref "SLOT6.1") (pin "1") (pinfunction "A15_1") (pintype "bidirectional"))
      (node (ref "SLOT6.2") (pin "1") (pinfunction "A15_1") (pintype "bidirectional"))
      (node (ref "SLOT7") (pin "17") (pinfunction "A15_17") (pintype "bidirectional"))
      (node (ref "U$1") (pin "B3") (pinfunction "A15_B3") (pintype "bidirectional"))
      (node (ref "U$2") (pin "B3") (pinfunction "A15_B3") (pintype "bidirectional"))
      (node (ref "X1") (pin "F") (pinfunction "A15_F") (pintype "bidirectional"))
    )
    (net (code "33") (name "BA16") (class "Default")
      (node (ref "IC2") (pin "1") (pinfunction "A_1") (pintype "input"))
      (node (ref "IC7") (pin "3") (pinfunction "O_3") (pintype "tri_state"))
      (node (ref "P1") (pin "C7") (pinfunction "A16_C7") (pintype "bidirectional"))
      (node (ref "P2") (pin "C7") (pinfunction "A16_C7") (pintype "bidirectional"))
      (node (ref "P3") (pin "C7") (pinfunction "A16_C7") (pintype "bidirectional"))
      (node (ref "P4") (pin "C7") (pinfunction "A16_C7") (pintype "bidirectional"))
      (node (ref "U$1") (pin "C3") (pinfunction "A16_C3") (pintype "bidirectional"))
      (node (ref "U$2") (pin "C3") (pinfunction "A16_C3") (pintype "bidirectional"))
    )
    (net (code "34") (name "BA17") (class "Default")
      (node (ref "IC2") (pin "2") (pinfunction "B_2") (pintype "input"))
      (node (ref "IC7") (pin "11") (pinfunction "O_11") (pintype "tri_state"))
      (node (ref "P1") (pin "C6") (pinfunction "A17_C6") (pintype "bidirectional"))
      (node (ref "P2") (pin "C6") (pinfunction "A17_C6") (pintype "bidirectional"))
      (node (ref "P3") (pin "C6") (pinfunction "A17_C6") (pintype "bidirectional"))
      (node (ref "P4") (pin "C6") (pinfunction "A17_C6") (pintype "bidirectional"))
      (node (ref "U$1") (pin "B2") (pinfunction "A17_B2") (pintype "bidirectional"))
      (node (ref "U$2") (pin "B2") (pinfunction "A17_B2") (pintype "bidirectional"))
    )
    (net (code "35") (name "BA18") (class "Default")
      (node (ref "IC2") (pin "3") (pinfunction "C_3") (pintype "input"))
      (node (ref "IC7") (pin "6") (pinfunction "O_6") (pintype "tri_state"))
      (node (ref "P1") (pin "C5") (pinfunction "A18_C5") (pintype "bidirectional"))
      (node (ref "P2") (pin "C5") (pinfunction "A18_C5") (pintype "bidirectional"))
      (node (ref "P3") (pin "C5") (pinfunction "A18_C5") (pintype "bidirectional"))
      (node (ref "P4") (pin "C5") (pinfunction "A18_C5") (pintype "bidirectional"))
      (node (ref "U$1") (pin "C2") (pinfunction "A18_C2") (pintype "bidirectional"))
      (node (ref "U$2") (pin "C2") (pinfunction "A18_C2") (pintype "bidirectional"))
    )
    (net (code "36") (name "BA19") (class "Default")
      (node (ref "IC2") (pin "4") (pinfunction "G2A_4") (pintype "input"))
      (node (ref "IC7") (pin "8") (pinfunction "O_8") (pintype "tri_state"))
      (node (ref "P1") (pin "C4") (pinfunction "A19_C4") (pintype "bidirectional"))
      (node (ref "P2") (pin "C4") (pinfunction "A19_C4") (pintype "bidirectional"))
      (node (ref "P3") (pin "C4") (pinfunction "A19_C4") (pintype "bidirectional"))
      (node (ref "P4") (pin "C4") (pinfunction "A19_C4") (pintype "bidirectional"))
      (node (ref "U$1") (pin "B1") (pinfunction "A19_B1") (pintype "bidirectional"))
      (node (ref "U$2") (pin "B1") (pinfunction "A19_B1") (pintype "bidirectional"))
    )
    (net (code "37") (name "BD0") (class "Default")
      (node (ref "P1") (pin "A22") (pinfunction "D0_A22") (pintype "bidirectional"))
      (node (ref "P2") (pin "A22") (pinfunction "D0_A22") (pintype "bidirectional"))
      (node (ref "P3") (pin "A22") (pinfunction "D0_A22") (pintype "bidirectional"))
      (node (ref "P4") (pin "A22") (pinfunction "D0_A22") (pintype "bidirectional"))
      (node (ref "SLOT3") (pin "B") (pinfunction "D0_B") (pintype "bidirectional"))
      (node (ref "SLOT5") (pin "B") (pinfunction "D0_B") (pintype "bidirectional"))
      (node (ref "SLOT6.1") (pin "27") (pinfunction "D0_27") (pintype "bidirectional"))
      (node (ref "SLOT6.2") (pin "27") (pinfunction "D0_27") (pintype "bidirectional"))
      (node (ref "SLOT7") (pin "B") (pinfunction "D0_B") (pintype "bidirectional"))
      (node (ref "U$1") (pin "A12") (pinfunction "D0_A12") (pintype "bidirectional"))
      (node (ref "U$2") (pin "A12") (pinfunction "D0_A12") (pintype "bidirectional"))
      (node (ref "X1") (pin "21") (pinfunction "D0_21") (pintype "bidirectional"))
    )
    (net (code "38") (name "BD1") (class "Default")
      (node (ref "P1") (pin "A21") (pinfunction "D1_A21") (pintype "bidirectional"))
      (node (ref "P2") (pin "A21") (pinfunction "D1_A21") (pintype "bidirectional"))
      (node (ref "P3") (pin "A21") (pinfunction "D1_A21") (pintype "bidirectional"))
      (node (ref "P4") (pin "A21") (pinfunction "D1_A21") (pintype "bidirectional"))
      (node (ref "SLOT3") (pin "C") (pinfunction "D1_C") (pintype "bidirectional"))
      (node (ref "SLOT5") (pin "C") (pinfunction "D1_C") (pintype "bidirectional"))
      (node (ref "SLOT6.1") (pin "28") (pinfunction "D1_28") (pintype "bidirectional"))
      (node (ref "SLOT6.2") (pin "28") (pinfunction "D1_28") (pintype "bidirectional"))
      (node (ref "SLOT7") (pin "C") (pinfunction "D1_C") (pintype "bidirectional"))
      (node (ref "U$1") (pin "A11") (pinfunction "D1_A11") (pintype "bidirectional"))
      (node (ref "U$2") (pin "A11") (pinfunction "D1_A11") (pintype "bidirectional"))
      (node (ref "X1") (pin "20") (pinfunction "D1_20") (pintype "bidirectional"))
    )
    (net (code "39") (name "BD2") (class "Default")
      (node (ref "P1") (pin "A20") (pinfunction "D2_A20") (pintype "bidirectional"))
      (node (ref "P2") (pin "A20") (pinfunction "D2_A20") (pintype "bidirectional"))
      (node (ref "P3") (pin "A20") (pinfunction "D2_A20") (pintype "bidirectional"))
      (node (ref "P4") (pin "A20") (pinfunction "D2_A20") (pintype "bidirectional"))
      (node (ref "SLOT3") (pin "D") (pinfunction "D2_D") (pintype "bidirectional"))
      (node (ref "SLOT5") (pin "D") (pinfunction "D2_D") (pintype "bidirectional"))
      (node (ref "SLOT6.1") (pin "29") (pinfunction "D2_29") (pintype "bidirectional"))
      (node (ref "SLOT6.2") (pin "29") (pinfunction "D2_29") (pintype "bidirectional"))
      (node (ref "SLOT7") (pin "D") (pinfunction "D2_D") (pintype "bidirectional"))
      (node (ref "U$1") (pin "A10") (pinfunction "D2_A10") (pintype "bidirectional"))
      (node (ref "U$2") (pin "A10") (pinfunction "D2_A10") (pintype "bidirectional"))
      (node (ref "X1") (pin "19") (pinfunction "D2_19") (pintype "bidirectional"))
    )
    (net (code "40") (name "BD3") (class "Default")
      (node (ref "P1") (pin "A19") (pinfunction "D3_A19") (pintype "bidirectional"))
      (node (ref "P2") (pin "A19") (pinfunction "D3_A19") (pintype "bidirectional"))
      (node (ref "P3") (pin "A19") (pinfunction "D3_A19") (pintype "bidirectional"))
      (node (ref "P4") (pin "A19") (pinfunction "D3_A19") (pintype "bidirectional"))
      (node (ref "SLOT3") (pin "E") (pinfunction "D3_E") (pintype "bidirectional"))
      (node (ref "SLOT5") (pin "E") (pinfunction "D3_E") (pintype "bidirectional"))
      (node (ref "SLOT6.1") (pin "30") (pinfunction "D3_30") (pintype "bidirectional"))
      (node (ref "SLOT6.2") (pin "30") (pinfunction "D3_30") (pintype "bidirectional"))
      (node (ref "SLOT7") (pin "E") (pinfunction "D3_E") (pintype "bidirectional"))
      (node (ref "U$1") (pin "A9") (pinfunction "D3_A9") (pintype "bidirectional"))
      (node (ref "U$2") (pin "A9") (pinfunction "D3_A9") (pintype "bidirectional"))
      (node (ref "X1") (pin "18") (pinfunction "D3_18") (pintype "bidirectional"))
    )
    (net (code "41") (name "BD4") (class "Default")
      (node (ref "P1") (pin "A18") (pinfunction "D4_A18") (pintype "bidirectional"))
      (node (ref "P2") (pin "A18") (pinfunction "D4_A18") (pintype "bidirectional"))
      (node (ref "P3") (pin "A18") (pinfunction "D4_A18") (pintype "bidirectional"))
      (node (ref "P4") (pin "A18") (pinfunction "D4_A18") (pintype "bidirectional"))
      (node (ref "SLOT3") (pin "F") (pinfunction "D4_F") (pintype "bidirectional"))
      (node (ref "SLOT5") (pin "F") (pinfunction "D4_F") (pintype "bidirectional"))
      (node (ref "SLOT6.1") (pin "31") (pinfunction "D4_31") (pintype "bidirectional"))
      (node (ref "SLOT6.2") (pin "31") (pinfunction "D4_31") (pintype "bidirectional"))
      (node (ref "SLOT7") (pin "F") (pinfunction "D4_F") (pintype "bidirectional"))
      (node (ref "U$1") (pin "A8") (pinfunction "D4_A8") (pintype "bidirectional"))
      (node (ref "U$2") (pin "A8") (pinfunction "D4_A8") (pintype "bidirectional"))
      (node (ref "X1") (pin "17") (pinfunction "D4_17") (pintype "bidirectional"))
    )
    (net (code "42") (name "BD5") (class "Default")
      (node (ref "P1") (pin "A17") (pinfunction "D5_A17") (pintype "bidirectional"))
      (node (ref "P2") (pin "A17") (pinfunction "D5_A17") (pintype "bidirectional"))
      (node (ref "P3") (pin "A17") (pinfunction "D5_A17") (pintype "bidirectional"))
      (node (ref "P4") (pin "A17") (pinfunction "D5_A17") (pintype "bidirectional"))
      (node (ref "SLOT3") (pin "G") (pinfunction "D5_G") (pintype "bidirectional"))
      (node (ref "SLOT5") (pin "G") (pinfunction "D5_G") (pintype "bidirectional"))
      (node (ref "SLOT6.1") (pin "32") (pinfunction "D5_32") (pintype "bidirectional"))
      (node (ref "SLOT6.2") (pin "32") (pinfunction "D5_32") (pintype "bidirectional"))
      (node (ref "SLOT7") (pin "G") (pinfunction "D5_G") (pintype "bidirectional"))
      (node (ref "U$1") (pin "A7") (pinfunction "D5_A7") (pintype "bidirectional"))
      (node (ref "U$2") (pin "A7") (pinfunction "D5_A7") (pintype "bidirectional"))
      (node (ref "X1") (pin "16") (pinfunction "D5_16") (pintype "bidirectional"))
    )
    (net (code "43") (name "BD6") (class "Default")
      (node (ref "P1") (pin "A16") (pinfunction "D6_A16") (pintype "bidirectional"))
      (node (ref "P2") (pin "A16") (pinfunction "D6_A16") (pintype "bidirectional"))
      (node (ref "P3") (pin "A16") (pinfunction "D6_A16") (pintype "bidirectional"))
      (node (ref "P4") (pin "A16") (pinfunction "D6_A16") (pintype "bidirectional"))
      (node (ref "SLOT3") (pin "H") (pinfunction "D6_H") (pintype "bidirectional"))
      (node (ref "SLOT5") (pin "H") (pinfunction "D6_H") (pintype "bidirectional"))
      (node (ref "SLOT6.1") (pin "33") (pinfunction "D6_33") (pintype "bidirectional"))
      (node (ref "SLOT6.2") (pin "33") (pinfunction "D6_33") (pintype "bidirectional"))
      (node (ref "SLOT7") (pin "H") (pinfunction "D6_H") (pintype "bidirectional"))
      (node (ref "U$1") (pin "A6") (pinfunction "D6_A6") (pintype "bidirectional"))
      (node (ref "U$2") (pin "A6") (pinfunction "D6_A6") (pintype "bidirectional"))
      (node (ref "X1") (pin "15") (pinfunction "D6_15") (pintype "bidirectional"))
    )
    (net (code "44") (name "BD7") (class "Default")
      (node (ref "P1") (pin "A15") (pinfunction "D7_A15") (pintype "bidirectional"))
      (node (ref "P2") (pin "A15") (pinfunction "D7_A15") (pintype "bidirectional"))
      (node (ref "P3") (pin "A15") (pinfunction "D7_A15") (pintype "bidirectional"))
      (node (ref "P4") (pin "A15") (pinfunction "D7_A15") (pintype "bidirectional"))
      (node (ref "SLOT3") (pin "J") (pinfunction "D7_J") (pintype "bidirectional"))
      (node (ref "SLOT5") (pin "J") (pinfunction "D7_J") (pintype "bidirectional"))
      (node (ref "SLOT6.1") (pin "34") (pinfunction "D7_34") (pintype "bidirectional"))
      (node (ref "SLOT6.2") (pin "34") (pinfunction "D7_34") (pintype "bidirectional"))
      (node (ref "SLOT7") (pin "J") (pinfunction "D7_J") (pintype "bidirectional"))
      (node (ref "U$1") (pin "A5") (pinfunction "D7_A5") (pintype "bidirectional"))
      (node (ref "U$2") (pin "A5") (pinfunction "D7_A5") (pintype "bidirectional"))
      (node (ref "X1") (pin "14") (pinfunction "D7_14") (pintype "bidirectional"))
    )
    (net (code "45") (name "BPHI0") (class "Default")
      (node (ref "P1") (pin "C28") (pinfunction "PHI0_C28") (pintype "bidirectional"))
      (node (ref "P2") (pin "C28") (pinfunction "PHI0_C28") (pintype "bidirectional"))
      (node (ref "P3") (pin "C28") (pinfunction "PHI0_C28") (pintype "bidirectional"))
      (node (ref "P4") (pin "C28") (pinfunction "PHI0_C28") (pintype "bidirectional"))
      (node (ref "U$1") (pin "C14") (pinfunction "PHI0_C14") (pintype "bidirectional"))
      (node (ref "U$2") (pin "C14") (pinfunction "PHI0_C14") (pintype "bidirectional"))
    )
    (net (code "46") (name "BPHI1") (class "Default")
      (node (ref "P1") (pin "C27") (pinfunction "PHI1_C27") (pintype "bidirectional"))
      (node (ref "P2") (pin "C27") (pinfunction "PHI1_C27") (pintype "bidirectional"))
      (node (ref "P3") (pin "C27") (pinfunction "PHI1_C27") (pintype "bidirectional"))
      (node (ref "P4") (pin "C27") (pinfunction "PHI1_C27") (pintype "bidirectional"))
      (node (ref "SLOT3") (pin "N") (pinfunction "PHI1_N") (pintype "bidirectional"))
      (node (ref "SLOT5") (pin "N") (pinfunction "PHI1_N") (pintype "bidirectional"))
      (node (ref "SLOT7") (pin "N") (pinfunction "PHI1_N") (pintype "bidirectional"))
      (node (ref "U$1") (pin "C13") (pinfunction "PHI1_C13") (pintype "bidirectional"))
      (node (ref "U$2") (pin "C13") (pinfunction "PHI1_C13") (pintype "bidirectional"))
    )
    (net (code "47") (name "BPHI2") (class "Default")
      (node (ref "IC6") (pin "12") (pinfunction "I0_12") (pintype "input"))
      (node (ref "IC6") (pin "2") (pinfunction "I1_2") (pintype "input"))
      (node (ref "IC6") (pin "4") (pinfunction "I0_4") (pintype "input"))
      (node (ref "IC6") (pin "9") (pinfunction "I0_9") (pintype "input"))
      (node (ref "P1") (pin "C26") (pinfunction "PHI2_C26") (pintype "bidirectional"))
      (node (ref "P2") (pin "C26") (pinfunction "PHI2_C26") (pintype "bidirectional"))
      (node (ref "P3") (pin "C26") (pinfunction "PHI2_C26") (pintype "bidirectional"))
      (node (ref "P4") (pin "C26") (pinfunction "PHI2_C26") (pintype "bidirectional"))
      (node (ref "SLOT3") (pin "L") (pinfunction "PHI0_L") (pintype "bidirectional"))
      (node (ref "SLOT5") (pin "L") (pinfunction "PHI0_L") (pintype "bidirectional"))
      (node (ref "SLOT7") (pin "L") (pinfunction "PHI0_L") (pintype "bidirectional"))
      (node (ref "U$1") (pin "C12") (pinfunction "PHI2_C12") (pintype "bidirectional"))
      (node (ref "U$2") (pin "C12") (pinfunction "PHI2_C12") (pintype "bidirectional"))
      (node (ref "X1") (pin "E") (pinfunction "PHI2_E") (pintype "input"))
    )
    (net (code "48") (name "COLORREF") (class "Default")
      (node (ref "SLOT3") (pin "Q") (pinfunction "COLORREF_Q") (pintype "bidirectional"))
      (node (ref "SLOT5") (pin "Q") (pinfunction "COLORREF_Q") (pintype "bidirectional"))
      (node (ref "SLOT7") (pin "Q") (pinfunction "COLORREF_Q") (pintype "bidirectional"))
    )
    (net (code "49") (name "GND") (class "Default")
      (node (ref "C1") (pin "-") (pinfunction "-_-") (pintype "passive"))
      (node (ref "C10") (pin "2") (pinfunction "2_2") (pintype "passive"))
      (node (ref "C11") (pin "2") (pinfunction "2_2") (pintype "passive"))
      (node (ref "C12") (pin "2") (pinfunction "2_2") (pintype "passive"))
      (node (ref "C13") (pin "-") (pinfunction "-_-") (pintype "passive"))
      (node (ref "C14") (pin "-") (pinfunction "-_-") (pintype "passive"))
      (node (ref "C15") (pin "-") (pinfunction "-_-") (pintype "passive"))
      (node (ref "C16") (pin "2") (pinfunction "2_2") (pintype "passive"))
      (node (ref "C17") (pin "-") (pinfunction "-_-") (pintype "passive"))
      (node (ref "C18") (pin "-") (pinfunction "-_-") (pintype "passive"))
      (node (ref "C19") (pin "-") (pinfunction "-_-") (pintype "passive"))
      (node (ref "C2") (pin "2") (pinfunction "2_2") (pintype "passive"))
      (node (ref "C20") (pin "-") (pinfunction "-_-") (pintype "passive"))
      (node (ref "C21") (pin "-") (pinfunction "-_-") (pintype "passive"))
      (node (ref "C22") (pin "2") (pinfunction "2_2") (pintype "passive"))
      (node (ref "C23") (pin "-") (pinfunction "-_-") (pintype "passive"))
      (node (ref "C24") (pin "-") (pinfunction "-_-") (pintype "passive"))
      (node (ref "C3") (pin "-") (pinfunction "-_-") (pintype "passive"))
      (node (ref "C4") (pin "-") (pinfunction "-_-") (pintype "passive"))
      (node (ref "C5") (pin "-") (pinfunction "-_-") (pintype "passive"))
      (node (ref "C6") (pin "-") (pinfunction "-_-") (pintype "passive"))
      (node (ref "C7") (pin "2") (pinfunction "2_2") (pintype "passive"))
      (node (ref "C8") (pin "2") (pinfunction "2_2") (pintype "passive"))
      (node (ref "C9") (pin "2") (pinfunction "2_2") (pintype "passive"))
      (node (ref "IC3") (pin "5") (pinfunction "G2B_5") (pintype "input"))
      (node (ref "IC4") (pin "5") (pinfunction "G2B_5") (pintype "input"))
      (node (ref "IC7") (pin "12") (pinfunction "I_12") (pintype "input"))
      (node (ref "IC7") (pin "2") (pinfunction "I_2") (pintype "input"))
      (node (ref "IC7") (pin "5") (pinfunction "I_5") (pintype "input"))
      (node (ref "IC7") (pin "9") (pinfunction "I_9") (pintype "input"))
      (node (ref "IC8") (pin "2") (pinfunction "I_2") (pintype "input"))
      (node (ref "IC8") (pin "5") (pinfunction "I_5") (pintype "input"))
      (node (ref "IC9") (pin "5") (pinfunction "G2B_5") (pintype "input"))
      (node (ref "J1") (pin "2") (pinfunction "2_2") (pintype "passive"))
      (node (ref "J1") (pin "3") (pinfunction "3_3") (pintype "passive"))
      (node (ref "JP1") (pin "1") (pinfunction "1_1") (pintype "passive"))
      (node (ref "JP1") (pin "2") (pinfunction "2_2") (pintype "passive"))
      (node (ref "JP1") (pin "3") (pinfunction "3_3") (pintype "passive"))
      (node (ref "JP9") (pin "1") (pinfunction "1_1") (pintype "passive"))
      (node (ref "P1") (pin "A1") (pinfunction "GND_A1") (pintype "bidirectional"))
      (node (ref "P1") (pin "A28") (pinfunction "GND2_A28") (pintype "bidirectional"))
      (node (ref "P1") (pin "A29") (pinfunction "GND3_A29") (pintype "bidirectional"))
      (node (ref "P1") (pin "A30") (pinfunction "GND4_A30") (pintype "bidirectional"))
      (node (ref "P1") (pin "A31") (pinfunction "GND5_A31") (pintype "bidirectional"))
      (node (ref "P1") (pin "A32") (pinfunction "GND6_A32") (pintype "bidirectional"))
      (node (ref "P1") (pin "C1") (pinfunction "GND7_C1") (pintype "bidirectional"))
      (node (ref "P1") (pin "C32") (pinfunction "GND8_C32") (pintype "bidirectional"))
      (node (ref "P2") (pin "A1") (pinfunction "GND_A1") (pintype "bidirectional"))
      (node (ref "P2") (pin "A28") (pinfunction "GND2_A28") (pintype "bidirectional"))
      (node (ref "P2") (pin "A29") (pinfunction "GND3_A29") (pintype "bidirectional"))
      (node (ref "P2") (pin "A30") (pinfunction "GND4_A30") (pintype "bidirectional"))
      (node (ref "P2") (pin "A31") (pinfunction "GND5_A31") (pintype "bidirectional"))
      (node (ref "P2") (pin "A32") (pinfunction "GND6_A32") (pintype "bidirectional"))
      (node (ref "P2") (pin "C1") (pinfunction "GND7_C1") (pintype "bidirectional"))
      (node (ref "P2") (pin "C32") (pinfunction "GND8_C32") (pintype "bidirectional"))
      (node (ref "P3") (pin "A1") (pinfunction "GND_A1") (pintype "bidirectional"))
      (node (ref "P3") (pin "A28") (pinfunction "GND2_A28") (pintype "bidirectional"))
      (node (ref "P3") (pin "A29") (pinfunction "GND3_A29") (pintype "bidirectional"))
      (node (ref "P3") (pin "A30") (pinfunction "GND4_A30") (pintype "bidirectional"))
      (node (ref "P3") (pin "A31") (pinfunction "GND5_A31") (pintype "bidirectional"))
      (node (ref "P3") (pin "A32") (pinfunction "GND6_A32") (pintype "bidirectional"))
      (node (ref "P3") (pin "C1") (pinfunction "GND7_C1") (pintype "bidirectional"))
      (node (ref "P3") (pin "C32") (pinfunction "GND8_C32") (pintype "bidirectional"))
      (node (ref "P4") (pin "A1") (pinfunction "GND_A1") (pintype "bidirectional"))
      (node (ref "P4") (pin "A28") (pinfunction "GND2_A28") (pintype "bidirectional"))
      (node (ref "P4") (pin "A29") (pinfunction "GND3_A29") (pintype "bidirectional"))
      (node (ref "P4") (pin "A30") (pinfunction "GND4_A30") (pintype "bidirectional"))
      (node (ref "P4") (pin "A31") (pinfunction "GND5_A31") (pintype "bidirectional"))
      (node (ref "P4") (pin "A32") (pinfunction "GND6_A32") (pintype "bidirectional"))
      (node (ref "P4") (pin "C1") (pinfunction "GND7_C1") (pintype "bidirectional"))
      (node (ref "P4") (pin "C32") (pinfunction "GND8_C32") (pintype "bidirectional"))
      (node (ref "SLOT3") (pin "Z") (pinfunction "GND_Z") (pintype "bidirectional"))
      (node (ref "SLOT5") (pin "Z") (pinfunction "GND_Z") (pintype "bidirectional"))
      (node (ref "SLOT6.1") (pin "17") (pinfunction "GND_17") (pintype "bidirectional"))
      (node (ref "SLOT6.2") (pin "17") (pinfunction "GND_17") (pintype "bidirectional"))
      (node (ref "SLOT7") (pin "Z") (pinfunction "GND_Z") (pintype "bidirectional"))
      (node (ref "U$1") (pin "A1") (pinfunction "GND_A1") (pintype "bidirectional"))
      (node (ref "U$1") (pin "A16") (pinfunction "GND2_A16") (pintype "bidirectional"))
      (node (ref "U$2") (pin "A1") (pinfunction "GND_A1") (pintype "bidirectional"))
      (node (ref "U$2") (pin "A16") (pinfunction "GND2_A16") (pintype "bidirectional"))
      (node (ref "X1") (pin "1") (pinfunction "GND_1") (pintype "power_in"))
      (node (ref "X1") (pin "22") (pinfunction "GND_22") (pintype "power_in"))
      (node (ref "X1") (pin "A") (pinfunction "GND_A") (pintype "power_in"))
      (node (ref "X1") (pin "Z") (pinfunction "GND_Z") (pintype "power_in"))
    )
    (net (code "50") (name "I2SCL") (class "Default")
      (node (ref "P1") (pin "A14") (pinfunction "I2CSCL_A14") (pintype "bidirectional"))
      (node (ref "P2") (pin "A14") (pinfunction "I2CSCL_A14") (pintype "bidirectional"))
      (node (ref "P3") (pin "A14") (pinfunction "I2CSCL_A14") (pintype "bidirectional"))
      (node (ref "P4") (pin "A14") (pinfunction "I2CSCL_A14") (pintype "bidirectional"))
    )
    (net (code "51") (name "I2SDA") (class "Default")
      (node (ref "P1") (pin "A13") (pinfunction "I2CSDA_A13") (pintype "bidirectional"))
      (node (ref "P2") (pin "A13") (pinfunction "I2CSDA_A13") (pintype "bidirectional"))
      (node (ref "P3") (pin "A13") (pinfunction "I2CSDA_A13") (pintype "bidirectional"))
      (node (ref "P4") (pin "A13") (pinfunction "I2CSDA_A13") (pintype "bidirectional"))
    )
    (net (code "52") (name "N$1") (class "Default")
      (node (ref "IC1") (pin "11") (pinfunction "I_11") (pintype "input"))
      (node (ref "JP14") (pin "2") (pinfunction "2_2") (pintype "passive"))
    )
    (net (code "53") (name "NOEXEC") (class "Default")
      (node (ref "P1") (pin "A10") (pinfunction "NOEXEC_A10") (pintype "bidirectional"))
      (node (ref "P2") (pin "A10") (pinfunction "NOEXEC_A10") (pintype "bidirectional"))
      (node (ref "P3") (pin "A10") (pinfunction "NOEXEC_A10") (pintype "bidirectional"))
      (node (ref "P4") (pin "A10") (pinfunction "NOEXEC_A10") (pintype "bidirectional"))
    )
    (net (code "54") (name "NOTMAPD") (class "Default")
      (node (ref "P1") (pin "A11") (pinfunction "NOTMAPD_A11") (pintype "bidirectional"))
      (node (ref "P2") (pin "A11") (pinfunction "NOTMAPD_A11") (pintype "bidirectional"))
      (node (ref "P3") (pin "A11") (pinfunction "NOTMAPD_A11") (pintype "bidirectional"))
      (node (ref "P4") (pin "A11") (pinfunction "NOTMAPD_A11") (pintype "bidirectional"))
    )
    (net (code "55") (name "Net-(IC1C-O)") (class "Default")
      (node (ref "IC1") (pin "6") (pinfunction "O_6") (pintype "output"))
      (node (ref "IC6") (pin "1") (pinfunction "I0_1") (pintype "input"))
    )
    (net (code "56") (name "Net-(IC1D-O)") (class "Default")
      (node (ref "IC1") (pin "8") (pinfunction "O_8") (pintype "output"))
      (node (ref "IC6") (pin "13") (pinfunction "I1_13") (pintype "input"))
    )
    (net (code "57") (name "Net-(IC1E-O)") (class "Default")
      (node (ref "IC1") (pin "10") (pinfunction "O_10") (pintype "output"))
      (node (ref "IC6") (pin "10") (pinfunction "I1_10") (pintype "input"))
    )
    (net (code "58") (name "Net-(IC4A-G2A)") (class "Default")
      (node (ref "IC4") (pin "4") (pinfunction "G2A_4") (pintype "input"))
      (node (ref "JP16") (pin "2") (pinfunction "2_2") (pintype "passive"))
    )
    (net (code "59") (name "Net-(IC5A-G2B)") (class "Default")
      (node (ref "IC5") (pin "5") (pinfunction "G2B_5") (pintype "input"))
      (node (ref "JP15") (pin "2") (pinfunction "2_2") (pintype "passive"))
    )
    (net (code "60") (name "Net-(IC5A-Y2)") (class "Default")
      (node (ref "IC5") (pin "13") (pinfunction "Y2_13") (pintype "output"))
      (node (ref "JP11") (pin "1") (pinfunction "1_1") (pintype "passive"))
    )
    (net (code "61") (name "Net-(IC5A-Y3)") (class "Default")
      (node (ref "IC5") (pin "12") (pinfunction "Y3_12") (pintype "output"))
      (node (ref "JP10") (pin "1") (pinfunction "1_1") (pintype "passive"))
    )
    (net (code "62") (name "Net-(IC5A-Y4)") (class "Default")
      (node (ref "IC5") (pin "11") (pinfunction "Y4_11") (pintype "output"))
      (node (ref "JP11") (pin "3") (pinfunction "3_3") (pintype "passive"))
    )
    (net (code "63") (name "Net-(IC5A-Y5)") (class "Default")
      (node (ref "IC5") (pin "10") (pinfunction "Y5_10") (pintype "output"))
      (node (ref "JP10") (pin "3") (pinfunction "3_3") (pintype "passive"))
    )
    (net (code "64") (name "Net-(IC7A-OE)") (class "Default")
      (node (ref "IC7") (pin "1") (pinfunction "OE_1") (pintype "input"))
      (node (ref "IC7") (pin "10") (pinfunction "OE_10") (pintype "input"))
      (node (ref "IC7") (pin "13") (pinfunction "OE_13") (pintype "input"))
      (node (ref "IC7") (pin "4") (pinfunction "OE_4") (pintype "input"))
      (node (ref "IC8") (pin "1") (pinfunction "OE_1") (pintype "input"))
      (node (ref "IC8") (pin "4") (pinfunction "OE_4") (pintype "input"))
      (node (ref "JP9") (pin "2") (pinfunction "2_2") (pintype "passive"))
    )
    (net (code "65") (name "Net-(IC9A-G2A)") (class "Default")
      (node (ref "IC9") (pin "4") (pinfunction "G2A_4") (pintype "input"))
      (node (ref "JP2") (pin "2") (pinfunction "2_2") (pintype "passive"))
    )
    (net (code "66") (name "Net-(IC9A-Y4)") (class "Default")
      (node (ref "IC9") (pin "11") (pinfunction "Y4_11") (pintype "output"))
      (node (ref "X1") (pin "11") (pinfunction "~{ROML}_11") (pintype "input"))
    )
    (net (code "67") (name "Net-(IC9A-Y7)") (class "Default")
      (node (ref "IC9") (pin "7") (pinfunction "Y7_7") (pintype "output"))
      (node (ref "X1") (pin "B") (pinfunction "~{ROMH}_B") (pintype "input"))
    )
    (net (code "68") (name "Net-(SLOT3-DMA_OUT)") (class "Default")
      (node (ref "SLOT3") (pin "24") (pinfunction "DMA_OUT_24") (pintype "bidirectional"))
      (node (ref "SLOT5") (pin "Y") (pinfunction "DMA_IN_Y") (pintype "bidirectional"))
    )
    (net (code "69") (name "Net-(SLOT3-INT_OUT)") (class "Default")
      (node (ref "SLOT3") (pin "23") (pinfunction "INT_OUT_23") (pintype "bidirectional"))
      (node (ref "SLOT5") (pin "X") (pinfunction "INT_IN_X") (pintype "bidirectional"))
    )
    (net (code "70") (name "Net-(SLOT5-DMA_OUT)") (class "Default")
      (node (ref "SLOT5") (pin "24") (pinfunction "DMA_OUT_24") (pintype "bidirectional"))
      (node (ref "SLOT7") (pin "Y") (pinfunction "DMA_IN_Y") (pintype "bidirectional"))
    )
    (net (code "71") (name "Net-(SLOT5-INT_OUT)") (class "Default")
      (node (ref "SLOT5") (pin "23") (pinfunction "INT_OUT_23") (pintype "bidirectional"))
      (node (ref "SLOT7") (pin "X") (pinfunction "INT_IN_X") (pintype "bidirectional"))
    )
    (net (code "72") (name "RC_CLK") (class "Default")
      (node (ref "SLOT6.1") (pin "21") (pinfunction "PHI0,CLK_21") (pintype "bidirectional"))
      (node (ref "SLOT6.2") (pin "21") (pinfunction "PHI0,CLK_21") (pintype "bidirectional"))
    )
    (net (code "73") (name "RDY") (class "Default")
      (node (ref "P1") (pin "A26") (pinfunction "RDY_A26") (pintype "bidirectional"))
      (node (ref "P2") (pin "A26") (pinfunction "RDY_A26") (pintype "bidirectional"))
      (node (ref "P3") (pin "A26") (pinfunction "RDY_A26") (pintype "bidirectional"))
      (node (ref "P4") (pin "A26") (pinfunction "RDY_A26") (pintype "bidirectional"))
      (node (ref "SLOT3") (pin "21") (pinfunction "RDY_21") (pintype "bidirectional"))
      (node (ref "SLOT5") (pin "21") (pinfunction "RDY_21") (pintype "bidirectional"))
      (node (ref "SLOT7") (pin "21") (pinfunction "RDY_21") (pintype "bidirectional"))
      (node (ref "U$1") (pin "B13") (pinfunction "RDY_B13") (pintype "bidirectional"))
      (node (ref "U$2") (pin "B13") (pinfunction "RDY_B13") (pintype "bidirectional"))
    )
    (net (code "74") (name "RX") (class "Default")
      (node (ref "SLOT6.1") (pin "36") (pinfunction "RX_36") (pintype "bidirectional"))
      (node (ref "SLOT6.2") (pin "36") (pinfunction "RX_36") (pintype "bidirectional"))
    )
    (net (code "75") (name "R{slash}-W") (class "Default")
      (node (ref "IC1") (pin "5") (pinfunction "I_5") (pintype "input"))
      (node (ref "IC6") (pin "5") (pinfunction "I1_5") (pintype "input"))
      (node (ref "P1") (pin "C25") (pinfunction "R/-W_C25") (pintype "bidirectional"))
      (node (ref "P2") (pin "C25") (pinfunction "R/-W_C25") (pintype "bidirectional"))
      (node (ref "P3") (pin "C25") (pinfunction "R/-W_C25") (pintype "bidirectional"))
      (node (ref "P4") (pin "C25") (pinfunction "R/-W_C25") (pintype "bidirectional"))
      (node (ref "SLOT3") (pin "18") (pinfunction "R/-W_18") (pintype "bidirectional"))
      (node (ref "SLOT5") (pin "18") (pinfunction "R/-W_18") (pintype "bidirectional"))
      (node (ref "SLOT7") (pin "18") (pinfunction "R/-W_18") (pintype "bidirectional"))
      (node (ref "U$1") (pin "B12") (pinfunction "R/-W_B12") (pintype "bidirectional"))
      (node (ref "U$2") (pin "B12") (pinfunction "R/-W_B12") (pintype "bidirectional"))
      (node (ref "X1") (pin "5") (pinfunction "R/~{W}_5") (pintype "bidirectional"))
    )
    (net (code "76") (name "SLOT0DEV") (class "Default")
      (node (ref "IC4") (pin "15") (pinfunction "Y0_15") (pintype "output"))
    )
    (net (code "77") (name "SLOT3DEV") (class "Default")
      (node (ref "IC4") (pin "12") (pinfunction "Y3_12") (pintype "output"))
      (node (ref "SLOT3") (pin "K") (pinfunction "/DEVSELECT_K") (pintype "bidirectional"))
    )
    (net (code "78") (name "SLOT5DEV") (class "Default")
      (node (ref "IC4") (pin "10") (pinfunction "Y5_10") (pintype "output"))
      (node (ref "SLOT5") (pin "K") (pinfunction "/DEVSELECT_K") (pintype "bidirectional"))
    )
    (net (code "79") (name "SLOT6DEV") (class "Default")
      (node (ref "IC4") (pin "9") (pinfunction "Y6_9") (pintype "output"))
    )
    (net (code "80") (name "SLOT7DEV") (class "Default")
      (node (ref "IC4") (pin "7") (pinfunction "Y7_7") (pintype "output"))
      (node (ref "SLOT7") (pin "K") (pinfunction "/DEVSELECT_K") (pintype "bidirectional"))
    )
    (net (code "81") (name "SYNC") (class "Default")
      (node (ref "IC1") (pin "3") (pinfunction "I_3") (pintype "input"))
      (node (ref "P1") (pin "C24") (pinfunction "SYNC_C24") (pintype "bidirectional"))
      (node (ref "P2") (pin "C24") (pinfunction "SYNC_C24") (pintype "bidirectional"))
      (node (ref "P3") (pin "C24") (pinfunction "SYNC_C24") (pintype "bidirectional"))
      (node (ref "P4") (pin "C24") (pinfunction "SYNC_C24") (pintype "bidirectional"))
      (node (ref "SLOT3") (pin "19") (pinfunction "SYNC_19") (pintype "bidirectional"))
      (node (ref "SLOT5") (pin "19") (pinfunction "SYNC_19") (pintype "bidirectional"))
      (node (ref "SLOT7") (pin "19") (pinfunction "SYNC_19") (pintype "bidirectional"))
      (node (ref "U$1") (pin "B11") (pinfunction "SYNC_B11") (pintype "bidirectional"))
      (node (ref "U$2") (pin "B11") (pinfunction "SYNC_B11") (pintype "bidirectional"))
    )
    (net (code "82") (name "TX") (class "Default")
      (node (ref "SLOT6.1") (pin "35") (pinfunction "TX_35") (pintype "bidirectional"))
      (node (ref "SLOT6.2") (pin "35") (pinfunction "TX_35") (pintype "bidirectional"))
    )
    (net (code "83") (name "USER1") (class "Default")
      (node (ref "SLOT6.1") (pin "37") (pinfunction "*/NMI,USER1_37") (pintype "bidirectional"))
      (node (ref "SLOT6.2") (pin "37") (pinfunction "*/NMI,USER1_37") (pintype "bidirectional"))
    )
    (net (code "84") (name "USER2") (class "Default")
      (node (ref "SLOT6.1") (pin "38") (pinfunction "EX1/USER2_38") (pintype "bidirectional"))
      (node (ref "SLOT6.2") (pin "38") (pinfunction "EX1/USER2_38") (pintype "bidirectional"))
    )
    (net (code "85") (name "USER3") (class "Default")
      (node (ref "SLOT6.1") (pin "39") (pinfunction "EX2/USER3_39") (pintype "bidirectional"))
      (node (ref "SLOT6.2") (pin "39") (pinfunction "EX2/USER3_39") (pintype "bidirectional"))
    )
    (net (code "86") (name "USER4") (class "Default")
      (node (ref "SLOT6.1") (pin "40") (pinfunction "USER4_40") (pintype "bidirectional"))
      (node (ref "SLOT6.2") (pin "40") (pinfunction "USER4_40") (pintype "bidirectional"))
    )
    (net (code "87") (name "VBUF") (class "Default")
      (node (ref "P1") (pin "A2") (pinfunction "VBUF_A2") (pintype "bidirectional"))
      (node (ref "P2") (pin "A2") (pinfunction "VBUF_A2") (pintype "bidirectional"))
      (node (ref "P3") (pin "A2") (pinfunction "VBUF_A2") (pintype "bidirectional"))
      (node (ref "P4") (pin "A2") (pinfunction "VBUF_A2") (pintype "bidirectional"))
      (node (ref "U$1") (pin "B15") (pinfunction "VBUF_B15") (pintype "bidirectional"))
      (node (ref "U$2") (pin "B15") (pinfunction "VBUF_B15") (pintype "bidirectional"))
    )
    (net (code "88") (name "VCC") (class "Default")
      (node (ref "C10") (pin "1") (pinfunction "1_1") (pintype "passive"))
      (node (ref "C11") (pin "1") (pinfunction "1_1") (pintype "passive"))
      (node (ref "C12") (pin "1") (pinfunction "1_1") (pintype "passive"))
      (node (ref "C13") (pin "+") (pinfunction "+_+") (pintype "passive"))
      (node (ref "C14") (pin "+") (pinfunction "+_+") (pintype "passive"))
      (node (ref "C15") (pin "+") (pinfunction "+_+") (pintype "passive"))
      (node (ref "C16") (pin "1") (pinfunction "1_1") (pintype "passive"))
      (node (ref "C17") (pin "+") (pinfunction "+_+") (pintype "passive"))
      (node (ref "C18") (pin "+") (pinfunction "+_+") (pintype "passive"))
      (node (ref "C2") (pin "1") (pinfunction "1_1") (pintype "passive"))
      (node (ref "C22") (pin "1") (pinfunction "1_1") (pintype "passive"))
      (node (ref "C23") (pin "+") (pinfunction "+_+") (pintype "passive"))
      (node (ref "C24") (pin "+") (pinfunction "+_+") (pintype "passive"))
      (node (ref "C3") (pin "+") (pinfunction "+_+") (pintype "passive"))
      (node (ref "C5") (pin "+") (pinfunction "+_+") (pintype "passive"))
      (node (ref "C7") (pin "1") (pinfunction "1_1") (pintype "passive"))
      (node (ref "C8") (pin "1") (pinfunction "1_1") (pintype "passive"))
      (node (ref "C9") (pin "1") (pinfunction "1_1") (pintype "passive"))
      (node (ref "IC2") (pin "6") (pinfunction "G1_6") (pintype "input"))
      (node (ref "IC3") (pin "6") (pinfunction "G1_6") (pintype "input"))
      (node (ref "IC9") (pin "6") (pinfunction "G1_6") (pintype "input"))
      (node (ref "J1") (pin "4") (pinfunction "4_4") (pintype "passive"))
      (node (ref "P1") (pin "C2") (pinfunction "VCC_C2") (pintype "bidirectional"))
      (node (ref "P1") (pin "C3") (pinfunction "VCC2_C3") (pintype "bidirectional"))
      (node (ref "P2") (pin "C2") (pinfunction "VCC_C2") (pintype "bidirectional"))
      (node (ref "P2") (pin "C3") (pinfunction "VCC2_C3") (pintype "bidirectional"))
      (node (ref "P3") (pin "C2") (pinfunction "VCC_C2") (pintype "bidirectional"))
      (node (ref "P3") (pin "C3") (pinfunction "VCC2_C3") (pintype "bidirectional"))
      (node (ref "P4") (pin "C2") (pinfunction "VCC_C2") (pintype "bidirectional"))
      (node (ref "P4") (pin "C3") (pinfunction "VCC2_C3") (pintype "bidirectional"))
      (node (ref "SLOT3") (pin "25") (pinfunction "5V_25") (pintype "bidirectional"))
      (node (ref "SLOT5") (pin "25") (pinfunction "5V_25") (pintype "bidirectional"))
      (node (ref "SLOT6.1") (pin "18") (pinfunction "VCC_18") (pintype "bidirectional"))
      (node (ref "SLOT6.2") (pin "18") (pinfunction "VCC_18") (pintype "bidirectional"))
      (node (ref "SLOT7") (pin "25") (pinfunction "5V_25") (pintype "bidirectional"))
      (node (ref "U$1") (pin "C1") (pinfunction "VCC_C1") (pintype "bidirectional"))
      (node (ref "U$1") (pin "C16") (pinfunction "VCC2_C16") (pintype "bidirectional"))
      (node (ref "U$2") (pin "C1") (pinfunction "VCC_C1") (pintype "bidirectional"))
      (node (ref "U$2") (pin "C16") (pinfunction "VCC2_C16") (pintype "bidirectional"))
      (node (ref "X1") (pin "2") (pinfunction "VCC_2") (pintype "power_in"))
      (node (ref "X1") (pin "3") (pinfunction "VCC_3") (pintype "power_in"))
    )
    (net (code "89") (name "VCC33") (class "Default")
      (node (ref "C1") (pin "+") (pinfunction "+_+") (pintype "passive"))
      (node (ref "C4") (pin "+") (pinfunction "+_+") (pintype "passive"))
      (node (ref "C6") (pin "+") (pinfunction "+_+") (pintype "passive"))
      (node (ref "P1") (pin "A9") (pinfunction "VCC33_A9") (pintype "bidirectional"))
      (node (ref "P2") (pin "A9") (pinfunction "VCC33_A9") (pintype "bidirectional"))
      (node (ref "P3") (pin "A9") (pinfunction "VCC33_A9") (pintype "bidirectional"))
      (node (ref "P4") (pin "A9") (pinfunction "VCC33_A9") (pintype "bidirectional"))
      (node (ref "U$1") (pin "B14") (pinfunction "VCC33_B14") (pintype "bidirectional"))
      (node (ref "U$2") (pin "B14") (pinfunction "VCC33_B14") (pintype "bidirectional"))
    )
    (net (code "90") (name "WPROT") (class "Default")
      (node (ref "P1") (pin "A12") (pinfunction "WPROT_A12") (pintype "bidirectional"))
      (node (ref "P2") (pin "A12") (pinfunction "WPROT_A12") (pintype "bidirectional"))
      (node (ref "P3") (pin "A12") (pinfunction "WPROT_A12") (pintype "bidirectional"))
      (node (ref "P4") (pin "A12") (pinfunction "WPROT_A12") (pintype "bidirectional"))
    )
    (net (code "91") (name "unconnected-(IC2A-Y7-Pad7)") (class "Default")
      (node (ref "IC2") (pin "7") (pinfunction "Y7_7") (pintype "output"))
    )
    (net (code "92") (name "unconnected-(IC4A-Y1-Pad14)") (class "Default")
      (node (ref "IC4") (pin "14") (pinfunction "Y1_14") (pintype "output"))
    )
    (net (code "93") (name "unconnected-(IC4A-Y2-Pad13)") (class "Default")
      (node (ref "IC4") (pin "13") (pinfunction "Y2_13") (pintype "output"))
    )
    (net (code "94") (name "unconnected-(IC4A-Y4-Pad11)") (class "Default")
      (node (ref "IC4") (pin "11") (pinfunction "Y4_11") (pintype "output"))
    )
    (net (code "95") (name "unconnected-(IC5A-Y0-Pad15)") (class "Default")
      (node (ref "IC5") (pin "15") (pinfunction "Y0_15") (pintype "output"))
    )
    (net (code "96") (name "unconnected-(IC5A-Y1-Pad14)") (class "Default")
      (node (ref "IC5") (pin "14") (pinfunction "Y1_14") (pintype "output"))
    )
    (net (code "97") (name "unconnected-(IC5A-Y6-Pad9)") (class "Default")
      (node (ref "IC5") (pin "9") (pinfunction "Y6_9") (pintype "output"))
    )
    (net (code "98") (name "unconnected-(IC5A-Y7-Pad7)") (class "Default")
      (node (ref "IC5") (pin "7") (pinfunction "Y7_7") (pintype "output"))
    )
    (net (code "99") (name "unconnected-(IC9A-Y0-Pad15)") (class "Default")
      (node (ref "IC9") (pin "15") (pinfunction "Y0_15") (pintype "output"))
    )
    (net (code "100") (name "unconnected-(IC9A-Y1-Pad14)") (class "Default")
      (node (ref "IC9") (pin "14") (pinfunction "Y1_14") (pintype "output"))
    )
    (net (code "101") (name "unconnected-(IC9A-Y2-Pad13)") (class "Default")
      (node (ref "IC9") (pin "13") (pinfunction "Y2_13") (pintype "output"))
    )
    (net (code "102") (name "unconnected-(IC9A-Y3-Pad12)") (class "Default")
      (node (ref "IC9") (pin "12") (pinfunction "Y3_12") (pintype "output"))
    )
    (net (code "103") (name "unconnected-(IC9A-Y5-Pad10)") (class "Default")
      (node (ref "IC9") (pin "10") (pinfunction "Y5_10") (pintype "output"))
    )
    (net (code "104") (name "unconnected-(IC9A-Y6-Pad9)") (class "Default")
      (node (ref "IC9") (pin "9") (pinfunction "Y6_9") (pintype "output"))
    )
    (net (code "105") (name "unconnected-(SLOT3--5V-PadR)") (class "Default")
      (node (ref "SLOT3") (pin "R") (pinfunction "-5V_R") (pintype "bidirectional"))
    )
    (net (code "106") (name "unconnected-(SLOT3--12V-PadS)") (class "Default")
      (node (ref "SLOT3") (pin "S") (pinfunction "-12V_S") (pintype "bidirectional"))
    )
    (net (code "107") (name "unconnected-(SLOT3-DMA_IN-PadY)") (class "Default")
      (node (ref "SLOT3") (pin "Y") (pinfunction "DMA_IN_Y") (pintype "bidirectional"))
    )
    (net (code "108") (name "unconnected-(SLOT3-INT_IN-PadX)") (class "Default")
      (node (ref "SLOT3") (pin "X") (pinfunction "INT_IN_X") (pintype "bidirectional"))
    )
    (net (code "109") (name "unconnected-(SLOT3-{slash}INH-PadT)") (class "Default")
      (node (ref "SLOT3") (pin "T") (pinfunction "/INH_T") (pintype "bidirectional"))
    )
    (net (code "110") (name "unconnected-(SLOT5--5V-PadR)") (class "Default")
      (node (ref "SLOT5") (pin "R") (pinfunction "-5V_R") (pintype "bidirectional"))
    )
    (net (code "111") (name "unconnected-(SLOT5--12V-PadS)") (class "Default")
      (node (ref "SLOT5") (pin "S") (pinfunction "-12V_S") (pintype "bidirectional"))
    )
    (net (code "112") (name "unconnected-(SLOT5-{slash}INH-PadT)") (class "Default")
      (node (ref "SLOT5") (pin "T") (pinfunction "/INH_T") (pintype "bidirectional"))
    )
    (net (code "113") (name "unconnected-(SLOT7--5V-PadR)") (class "Default")
      (node (ref "SLOT7") (pin "R") (pinfunction "-5V_R") (pintype "bidirectional"))
    )
    (net (code "114") (name "unconnected-(SLOT7--12V-PadS)") (class "Default")
      (node (ref "SLOT7") (pin "S") (pinfunction "-12V_S") (pintype "bidirectional"))
    )
    (net (code "115") (name "unconnected-(SLOT7-DMA_OUT-Pad24)") (class "Default")
      (node (ref "SLOT7") (pin "24") (pinfunction "DMA_OUT_24") (pintype "bidirectional"))
    )
    (net (code "116") (name "unconnected-(SLOT7-INT_OUT-Pad23)") (class "Default")
      (node (ref "SLOT7") (pin "23") (pinfunction "INT_OUT_23") (pintype "bidirectional"))
    )
    (net (code "117") (name "unconnected-(SLOT7-{slash}INH-PadT)") (class "Default")
      (node (ref "SLOT7") (pin "T") (pinfunction "/INH_T") (pintype "bidirectional"))
    )
    (net (code "118") (name "unconnected-(X1A-BA-Pad12)") (class "Default")
      (node (ref "X1") (pin "12") (pinfunction "BA_12") (pintype "input"))
    )
    (net (code "119") (name "unconnected-(X1A-DMA-Pad13)") (class "Default")
      (node (ref "X1") (pin "13") (pinfunction "DMA_13") (pintype "bidirectional"))
    )
    (net (code "120") (name "unconnected-(X1A-~{EXROM}-Pad9)") (class "Default")
      (node (ref "X1") (pin "9") (pinfunction "~{EXROM}_9") (pintype "input"))
    )
    (net (code "121") (name "unconnected-(X1A-~{GAME}-Pad8)") (class "Default")
      (node (ref "X1") (pin "8") (pinfunction "~{GAME}_8") (pintype "input"))
    )
    (net (code "122") (name "{slash}BANK0") (class "Default")
      (node (ref "IC2") (pin "15") (pinfunction "Y0_15") (pintype "output"))
      (node (ref "JP14") (pin "1") (pinfunction "1_1") (pintype "passive"))
      (node (ref "JP15") (pin "1") (pinfunction "1_1") (pintype "passive"))
    )
    (net (code "123") (name "{slash}BANK1") (class "Default")
      (node (ref "IC2") (pin "14") (pinfunction "Y1_14") (pintype "output"))
      (node (ref "JP2") (pin "1") (pinfunction "1_1") (pintype "passive"))
    )
    (net (code "124") (name "{slash}BANK2") (class "Default")
      (node (ref "IC2") (pin "13") (pinfunction "Y2_13") (pintype "output"))
      (node (ref "JP15") (pin "3") (pinfunction "3_3") (pintype "passive"))
    )
    (net (code "125") (name "{slash}BANK3") (class "Default")
      (node (ref "IC2") (pin "12") (pinfunction "Y3_12") (pintype "output"))
      (node (ref "JP2") (pin "3") (pinfunction "3_3") (pintype "passive"))
    )
    (net (code "126") (name "{slash}BANK4") (class "Default")
      (node (ref "IC2") (pin "11") (pinfunction "Y4_11") (pintype "output"))
    )
    (net (code "127") (name "{slash}BANK5") (class "Default")
      (node (ref "IC2") (pin "10") (pinfunction "Y5_10") (pintype "output"))
    )
    (net (code "128") (name "{slash}BANK6") (class "Default")
      (node (ref "IC2") (pin "9") (pinfunction "Y6_9") (pintype "output"))
      (node (ref "JP14") (pin "3") (pinfunction "3_3") (pintype "passive"))
    )
    (net (code "129") (name "{slash}BE") (class "Default")
      (node (ref "IC8") (pin "3") (pinfunction "O_3") (pintype "tri_state"))
      (node (ref "P1") (pin "A8") (pinfunction "/BE_A8") (pintype "bidirectional"))
      (node (ref "P2") (pin "A8") (pinfunction "/BE_A8") (pintype "bidirectional"))
      (node (ref "P3") (pin "A8") (pinfunction "/BE_A8") (pintype "bidirectional"))
      (node (ref "P4") (pin "A8") (pinfunction "/BE_A8") (pintype "bidirectional"))
      (node (ref "U$1") (pin "A4") (pinfunction "/BE_A4") (pintype "bidirectional"))
      (node (ref "U$2") (pin "A4") (pinfunction "/BE_A4") (pintype "bidirectional"))
    )
    (net (code "130") (name "{slash}DMA") (class "Default")
      (node (ref "JP9") (pin "3") (pinfunction "3_3") (pintype "passive"))
      (node (ref "SLOT3") (pin "22") (pinfunction "/DMA_22") (pintype "bidirectional"))
      (node (ref "SLOT5") (pin "22") (pinfunction "/DMA_22") (pintype "bidirectional"))
      (node (ref "SLOT7") (pin "22") (pinfunction "/DMA_22") (pintype "bidirectional"))
    )
    (net (code "131") (name "{slash}EXTIO") (class "Default")
      (node (ref "P1") (pin "A5") (pinfunction "/EXTIO_A5") (pintype "bidirectional"))
      (node (ref "P2") (pin "A5") (pinfunction "/EXTIO_A5") (pintype "bidirectional"))
      (node (ref "P3") (pin "A5") (pinfunction "/EXTIO_A5") (pintype "bidirectional"))
      (node (ref "P4") (pin "A5") (pinfunction "/EXTIO_A5") (pintype "bidirectional"))
    )
    (net (code "132") (name "{slash}IOINH") (class "Default")
      (node (ref "JP8") (pin "1") (pinfunction "1_1") (pintype "passive"))
      (node (ref "P1") (pin "A4") (pinfunction "/IOINH_A4") (pintype "bidirectional"))
      (node (ref "P2") (pin "A4") (pinfunction "/IOINH_A4") (pintype "bidirectional"))
      (node (ref "P3") (pin "A4") (pinfunction "/IOINH_A4") (pintype "bidirectional"))
      (node (ref "P4") (pin "A4") (pinfunction "/IOINH_A4") (pintype "bidirectional"))
    )
    (net (code "133") (name "{slash}IOSEL") (class "Default")
      (node (ref "JP16") (pin "3") (pinfunction "3_3") (pintype "passive"))
      (node (ref "JP17") (pin "2") (pinfunction "2_2") (pintype "passive"))
      (node (ref "P1") (pin "A7") (pinfunction "/IOSEL_A7") (pintype "bidirectional"))
      (node (ref "P2") (pin "A7") (pinfunction "/IOSEL_A7") (pintype "bidirectional"))
      (node (ref "P3") (pin "A7") (pinfunction "/IOSEL_A7") (pintype "bidirectional"))
      (node (ref "P4") (pin "A7") (pinfunction "/IOSEL_A7") (pintype "bidirectional"))
      (node (ref "U$1") (pin "A3") (pinfunction "/IOSEL_A3") (pintype "bidirectional"))
      (node (ref "U$2") (pin "A3") (pinfunction "/IOSEL_A3") (pintype "bidirectional"))
    )
    (net (code "134") (name "{slash}IOSTROBE") (class "Default")
      (node (ref "JP10") (pin "2") (pinfunction "2_2") (pintype "passive"))
      (node (ref "SLOT3") (pin "20") (pinfunction "/IOSTROBE_20") (pintype "bidirectional"))
      (node (ref "SLOT5") (pin "20") (pinfunction "/IOSTROBE_20") (pintype "bidirectional"))
      (node (ref "SLOT7") (pin "20") (pinfunction "/IOSTROBE_20") (pintype "bidirectional"))
    )
    (net (code "135") (name "{slash}IRQ") (class "Default")
      (node (ref "P1") (pin "A24") (pinfunction "/IRQ_A24") (pintype "bidirectional"))
      (node (ref "P2") (pin "A24") (pinfunction "/IRQ_A24") (pintype "bidirectional"))
      (node (ref "P3") (pin "A24") (pinfunction "/IRQ_A24") (pintype "bidirectional"))
      (node (ref "P4") (pin "A24") (pinfunction "/IRQ_A24") (pintype "bidirectional"))
      (node (ref "SLOT3") (pin "V") (pinfunction "/IRQ_V") (pintype "bidirectional"))
      (node (ref "SLOT5") (pin "V") (pinfunction "/IRQ_V") (pintype "bidirectional"))
      (node (ref "SLOT6.1") (pin "22") (pinfunction "/IRQ_22") (pintype "bidirectional"))
      (node (ref "SLOT6.2") (pin "22") (pinfunction "/IRQ_22") (pintype "bidirectional"))
      (node (ref "SLOT7") (pin "V") (pinfunction "/IRQ_V") (pintype "bidirectional"))
      (node (ref "U$1") (pin "A14") (pinfunction "/IRQ_A14") (pintype "bidirectional"))
      (node (ref "U$2") (pin "A14") (pinfunction "/IRQ_A14") (pintype "bidirectional"))
      (node (ref "X1") (pin "4") (pinfunction "~{IRQ}_4") (pintype "bidirectional"))
    )
    (net (code "136") (name "{slash}M1") (class "Default")
      (node (ref "IC1") (pin "4") (pinfunction "O_4") (pintype "output"))
      (node (ref "SLOT6.1") (pin "19") (pinfunction "*PHI2,/M1_19") (pintype "bidirectional"))
      (node (ref "SLOT6.2") (pin "19") (pinfunction "*PHI2,/M1_19") (pintype "bidirectional"))
    )
    (net (code "137") (name "{slash}MEMSEL") (class "Default")
      (node (ref "IC2") (pin "5") (pinfunction "G2B_5") (pintype "input"))
      (node (ref "IC8") (pin "6") (pinfunction "O_6") (pintype "tri_state"))
      (node (ref "P1") (pin "A6") (pinfunction "/MEMSEL_A6") (pintype "bidirectional"))
      (node (ref "P2") (pin "A6") (pinfunction "/MEMSEL_A6") (pintype "bidirectional"))
      (node (ref "P3") (pin "A6") (pinfunction "/MEMSEL_A6") (pintype "bidirectional"))
      (node (ref "P4") (pin "A6") (pinfunction "/MEMSEL_A6") (pintype "bidirectional"))
      (node (ref "U$1") (pin "A2") (pinfunction "/MEMSEL_A2") (pintype "bidirectional"))
      (node (ref "U$2") (pin "A2") (pinfunction "/MEMSEL_A2") (pintype "bidirectional"))
    )
    (net (code "138") (name "{slash}NMI") (class "Default")
      (node (ref "P1") (pin "A23") (pinfunction "/NMI_A23") (pintype "bidirectional"))
      (node (ref "P2") (pin "A23") (pinfunction "/NMI_A23") (pintype "bidirectional"))
      (node (ref "P3") (pin "A23") (pinfunction "/NMI_A23") (pintype "bidirectional"))
      (node (ref "P4") (pin "A23") (pinfunction "/NMI_A23") (pintype "bidirectional"))
      (node (ref "SLOT3") (pin "W") (pinfunction "/NMI_W") (pintype "bidirectional"))
      (node (ref "SLOT5") (pin "W") (pinfunction "/NMI_W") (pintype "bidirectional"))
      (node (ref "SLOT7") (pin "W") (pinfunction "/NMI_W") (pintype "bidirectional"))
      (node (ref "U$1") (pin "A13") (pinfunction "/NMI_A13") (pintype "bidirectional"))
      (node (ref "U$2") (pin "A13") (pinfunction "/NMI_A13") (pintype "bidirectional"))
      (node (ref "X1") (pin "D") (pinfunction "~{NMI}_D") (pintype "bidirectional"))
    )
    (net (code "139") (name "{slash}RD0") (class "Default")
      (node (ref "IC6") (pin "6") (pinfunction "O_6") (pintype "output"))
      (node (ref "SLOT6.1") (pin "25") (pinfunction "*RDY,/RD_25") (pintype "bidirectional"))
      (node (ref "SLOT6.2") (pin "25") (pinfunction "*RDY,/RD_25") (pintype "bidirectional"))
    )
    (net (code "140") (name "{slash}RES") (class "Default")
      (node (ref "P1") (pin "A27") (pinfunction "/RES_A27") (pintype "bidirectional"))
      (node (ref "P2") (pin "A27") (pinfunction "/RES_A27") (pintype "bidirectional"))
      (node (ref "P3") (pin "A27") (pinfunction "/RES_A27") (pintype "bidirectional"))
      (node (ref "P4") (pin "A27") (pinfunction "/RES_A27") (pintype "bidirectional"))
      (node (ref "SLOT3") (pin "U") (pinfunction "/RES_U") (pintype "bidirectional"))
      (node (ref "SLOT5") (pin "U") (pinfunction "/RES_U") (pintype "bidirectional"))
      (node (ref "SLOT6.1") (pin "20") (pinfunction "/RES_20") (pintype "bidirectional"))
      (node (ref "SLOT6.2") (pin "20") (pinfunction "/RES_20") (pintype "bidirectional"))
      (node (ref "SLOT7") (pin "U") (pinfunction "/RES_U") (pintype "bidirectional"))
      (node (ref "U$1") (pin "A15") (pinfunction "/RES_A15") (pintype "bidirectional"))
      (node (ref "U$2") (pin "A15") (pinfunction "/RES_A15") (pintype "bidirectional"))
      (node (ref "X1") (pin "C") (pinfunction "~{RESET}_C") (pintype "input"))
    )
    (net (code "141") (name "{slash}SLOT0IO") (class "Default")
      (node (ref "IC3") (pin "15") (pinfunction "Y0_15") (pintype "output"))
      (node (ref "JP16") (pin "1") (pinfunction "1_1") (pintype "passive"))
    )
    (net (code "142") (name "{slash}SLOT1IO") (class "Default")
      (node (ref "IC3") (pin "14") (pinfunction "Y1_14") (pintype "output"))
      (node (ref "X1") (pin "7") (pinfunction "~{IO1}_7") (pintype "input"))
    )
    (net (code "143") (name "{slash}SLOT2IO") (class "Default")
      (node (ref "IC3") (pin "13") (pinfunction "Y2_13") (pintype "output"))
      (node (ref "JP17") (pin "1") (pinfunction "1_1") (pintype "passive"))
    )
    (net (code "144") (name "{slash}SLOT3IO") (class "Default")
      (node (ref "IC3") (pin "12") (pinfunction "Y3_12") (pintype "output"))
      (node (ref "SLOT3") (pin "1") (pinfunction "/IOSELECT_1") (pintype "bidirectional"))
    )
    (net (code "145") (name "{slash}SLOT4IO") (class "Default")
      (node (ref "IC3") (pin "11") (pinfunction "Y4_11") (pintype "output"))
      (node (ref "X1") (pin "10") (pinfunction "~{IO2}_10") (pintype "input"))
    )
    (net (code "146") (name "{slash}SLOT5IO") (class "Default")
      (node (ref "IC3") (pin "10") (pinfunction "Y5_10") (pintype "output"))
      (node (ref "SLOT5") (pin "1") (pinfunction "/IOSELECT_1") (pintype "bidirectional"))
    )
    (net (code "147") (name "{slash}SLOT6.X_BANK") (class "Default")
      (node (ref "IC6") (pin "8") (pinfunction "O_8") (pintype "output"))
      (node (ref "SLOT6.1") (pin "23") (pinfunction "*PHI1,/MREQ_23") (pintype "bidirectional"))
      (node (ref "SLOT6.2") (pin "23") (pinfunction "*PHI1,/MREQ_23") (pintype "bidirectional"))
    )
    (net (code "148") (name "{slash}SLOT6.X_IO") (class "Default")
      (node (ref "IC6") (pin "11") (pinfunction "O_11") (pintype "output"))
      (node (ref "SLOT6.1") (pin "26") (pinfunction "*SYNC,/IOREQ_26") (pintype "bidirectional"))
      (node (ref "SLOT6.2") (pin "26") (pinfunction "*SYNC,/IOREQ_26") (pintype "bidirectional"))
    )
    (net (code "149") (name "{slash}SLOT6IO") (class "Default")
      (node (ref "IC1") (pin "9") (pinfunction "I_9") (pintype "input"))
      (node (ref "IC3") (pin "9") (pinfunction "Y6_9") (pintype "output"))
    )
    (net (code "150") (name "{slash}SLOT7IO") (class "Default")
      (node (ref "IC3") (pin "7") (pinfunction "Y7_7") (pintype "output"))
      (node (ref "SLOT7") (pin "1") (pinfunction "/IOSELECT_1") (pintype "bidirectional"))
    )
    (net (code "151") (name "{slash}SLOTIO") (class "Default")
      (node (ref "IC3") (pin "4") (pinfunction "G2A_4") (pintype "input"))
      (node (ref "JP11") (pin "2") (pinfunction "2_2") (pintype "passive"))
    )
    (net (code "152") (name "{slash}SO") (class "Default")
      (node (ref "P1") (pin "A25") (pinfunction "/SO_A25") (pintype "bidirectional"))
      (node (ref "P2") (pin "A25") (pinfunction "/SO_A25") (pintype "bidirectional"))
      (node (ref "P3") (pin "A25") (pinfunction "/SO_A25") (pintype "bidirectional"))
      (node (ref "P4") (pin "A25") (pinfunction "/SO_A25") (pintype "bidirectional"))
    )
    (net (code "153") (name "{slash}WR0") (class "Default")
      (node (ref "IC6") (pin "3") (pinfunction "O_3") (pintype "output"))
      (node (ref "SLOT6.1") (pin "24") (pinfunction "*R/-W,/WR_24") (pintype "bidirectional"))
      (node (ref "SLOT6.2") (pin "24") (pinfunction "*R/-W,/WR_24") (pintype "bidirectional"))
    )
  )
)
